# ASIC_3.net
KiCad netlist of a schematic drawn in Altium Designer
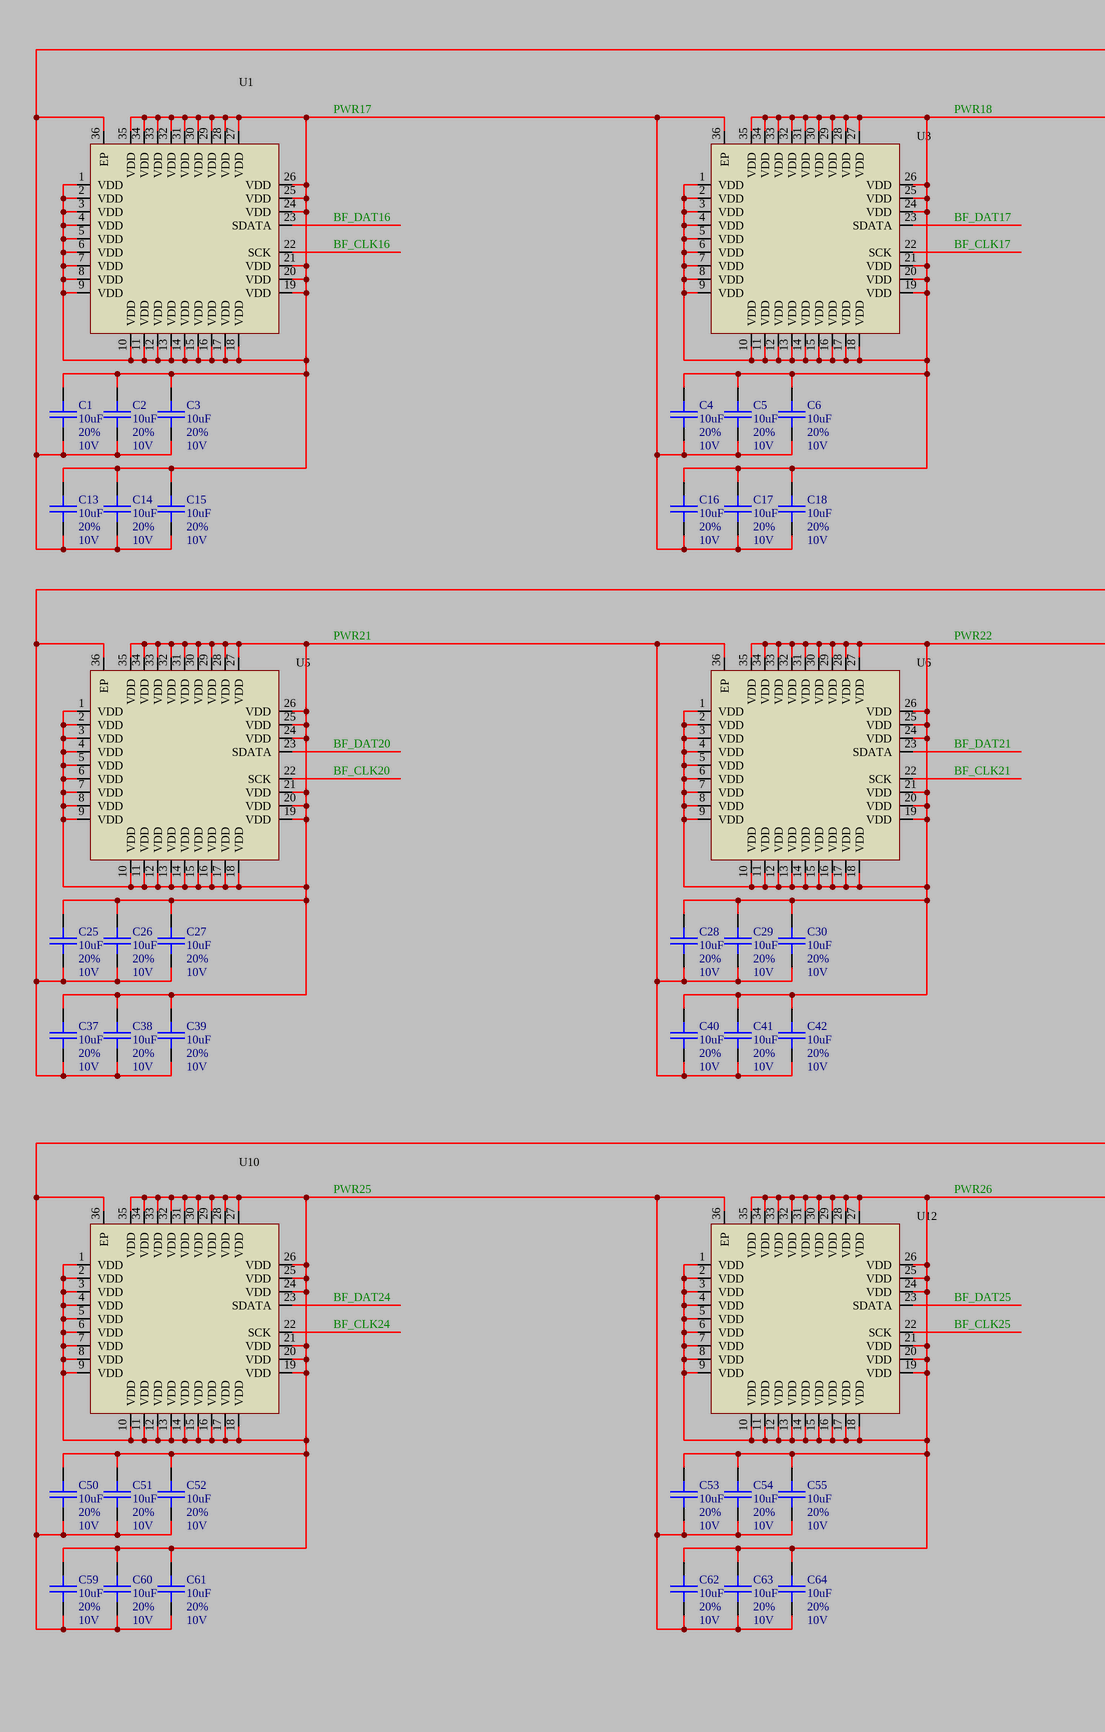
[diagram p0: ASIC_3.SchDoc, left]
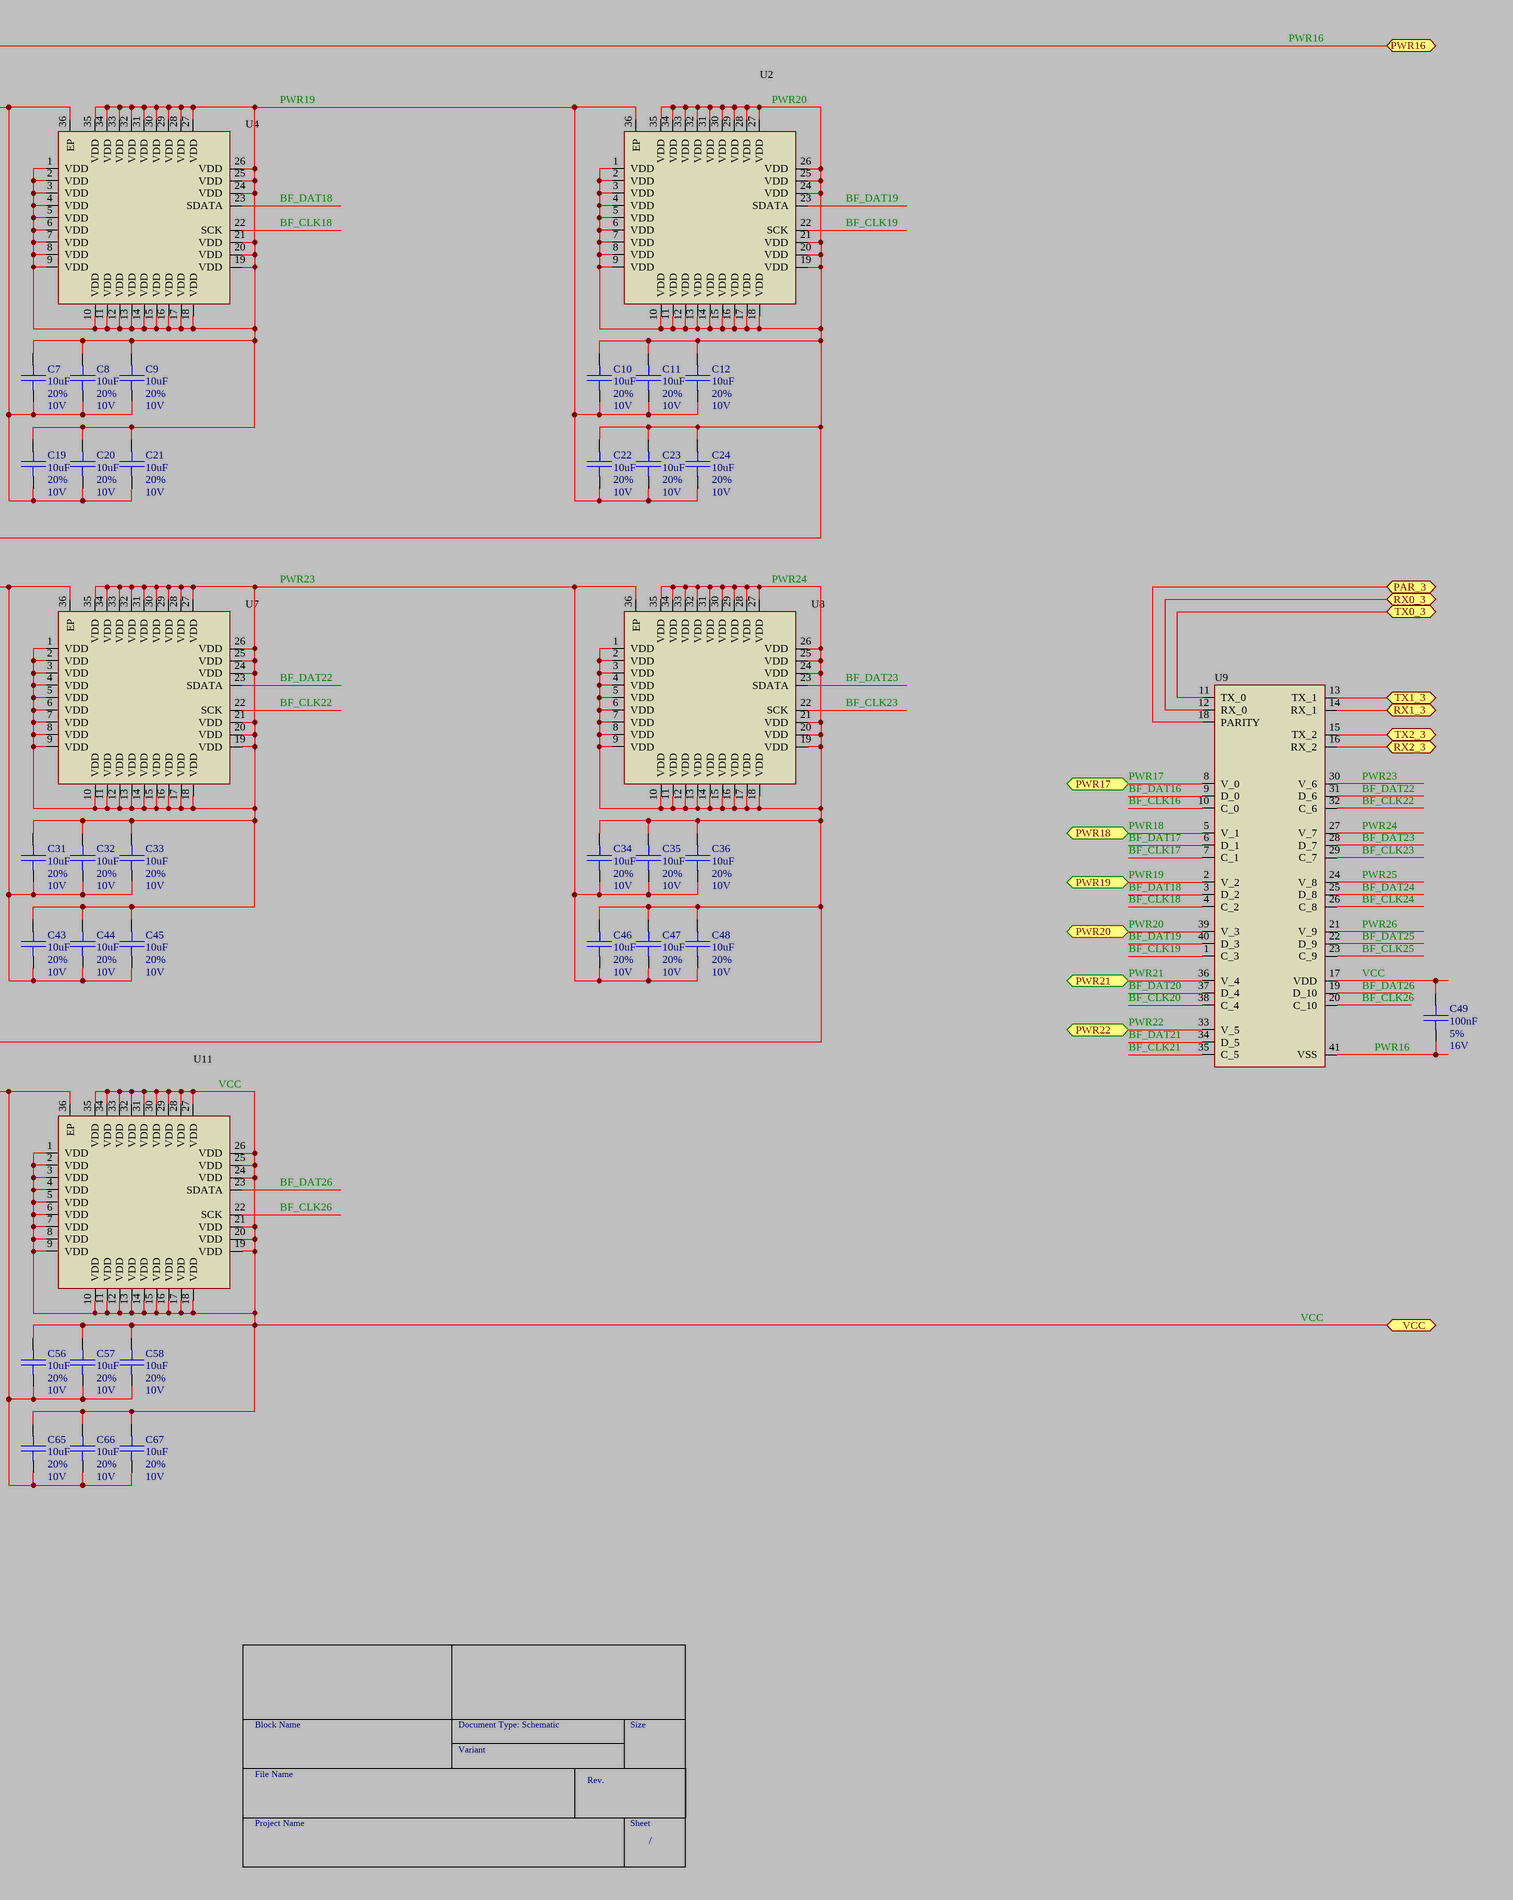
[diagram p1: ASIC_3.SchDoc, right]

(export (version "E")
  (design (tool "Eeschema 10.0.6"))
  (components
    (comp (ref "C1")
      (value "C")
      (footprint "SMD_0402_CAPC1005X70N")
      (fields
        (field (name "DB_PART_NUMBER") "CAP000047481")
        (field (name "DB_VALUE") "10uF")
        (field (name "DB_TOLERANCE") "20%")
        (field (name "DB_VOLTAGE") "10V")
        (field (name "DB_MANUFACTURER_PART") "SAMSUNG    CL05A106MP5NUNC")
        (field (name "DB_APPROVED_BY") "VSN")
      )
      (libsource (lib "Database_Libs1") (part "C"))
    )
    (comp (ref "C2")
      (value "C")
      (footprint "SMD_0402_CAPC1005X70N")
      (fields
        (field (name "DB_PART_NUMBER") "CAP000047481")
        (field (name "DB_VALUE") "10uF")
        (field (name "DB_TOLERANCE") "20%")
        (field (name "DB_VOLTAGE") "10V")
        (field (name "DB_MANUFACTURER_PART") "SAMSUNG    CL05A106MP5NUNC")
        (field (name "DB_APPROVED_BY") "VSN")
      )
      (libsource (lib "Database_Libs1") (part "C"))
    )
    (comp (ref "C3")
      (value "C")
      (footprint "SMD_0402_CAPC1005X70N")
      (fields
        (field (name "DB_PART_NUMBER") "CAP000047481")
        (field (name "DB_VALUE") "10uF")
        (field (name "DB_TOLERANCE") "20%")
        (field (name "DB_VOLTAGE") "10V")
        (field (name "DB_MANUFACTURER_PART") "SAMSUNG    CL05A106MP5NUNC")
        (field (name "DB_APPROVED_BY") "VSN")
      )
      (libsource (lib "Database_Libs1") (part "C"))
    )
    (comp (ref "C4")
      (value "C")
      (footprint "SMD_0402_CAPC1005X70N")
      (fields
        (field (name "DB_PART_NUMBER") "CAP000047481")
        (field (name "DB_VALUE") "10uF")
        (field (name "DB_TOLERANCE") "20%")
        (field (name "DB_VOLTAGE") "10V")
        (field (name "DB_MANUFACTURER_PART") "SAMSUNG    CL05A106MP5NUNC")
        (field (name "DB_APPROVED_BY") "VSN")
      )
      (libsource (lib "Database_Libs1") (part "C"))
    )
    (comp (ref "C5")
      (value "C")
      (footprint "SMD_0402_CAPC1005X70N")
      (fields
        (field (name "DB_PART_NUMBER") "CAP000047481")
        (field (name "DB_VALUE") "10uF")
        (field (name "DB_TOLERANCE") "20%")
        (field (name "DB_VOLTAGE") "10V")
        (field (name "DB_MANUFACTURER_PART") "SAMSUNG    CL05A106MP5NUNC")
        (field (name "DB_APPROVED_BY") "VSN")
      )
      (libsource (lib "Database_Libs1") (part "C"))
    )
    (comp (ref "C6")
      (value "C")
      (footprint "SMD_0402_CAPC1005X70N")
      (fields
        (field (name "DB_PART_NUMBER") "CAP000047481")
        (field (name "DB_VALUE") "10uF")
        (field (name "DB_TOLERANCE") "20%")
        (field (name "DB_VOLTAGE") "10V")
        (field (name "DB_MANUFACTURER_PART") "SAMSUNG    CL05A106MP5NUNC")
        (field (name "DB_APPROVED_BY") "VSN")
      )
      (libsource (lib "Database_Libs1") (part "C"))
    )
    (comp (ref "C7")
      (value "C")
      (footprint "SMD_0402_CAPC1005X70N")
      (fields
        (field (name "DB_PART_NUMBER") "CAP000047481")
        (field (name "DB_VALUE") "10uF")
        (field (name "DB_TOLERANCE") "20%")
        (field (name "DB_VOLTAGE") "10V")
        (field (name "DB_MANUFACTURER_PART") "SAMSUNG    CL05A106MP5NUNC")
        (field (name "DB_APPROVED_BY") "VSN")
      )
      (libsource (lib "Database_Libs1") (part "C"))
    )
    (comp (ref "C8")
      (value "C")
      (footprint "SMD_0402_CAPC1005X70N")
      (fields
        (field (name "DB_PART_NUMBER") "CAP000047481")
        (field (name "DB_VALUE") "10uF")
        (field (name "DB_TOLERANCE") "20%")
        (field (name "DB_VOLTAGE") "10V")
        (field (name "DB_MANUFACTURER_PART") "SAMSUNG    CL05A106MP5NUNC")
        (field (name "DB_APPROVED_BY") "VSN")
      )
      (libsource (lib "Database_Libs1") (part "C"))
    )
    (comp (ref "C9")
      (value "C")
      (footprint "SMD_0402_CAPC1005X70N")
      (fields
        (field (name "DB_PART_NUMBER") "CAP000047481")
        (field (name "DB_VALUE") "10uF")
        (field (name "DB_TOLERANCE") "20%")
        (field (name "DB_VOLTAGE") "10V")
        (field (name "DB_MANUFACTURER_PART") "SAMSUNG    CL05A106MP5NUNC")
        (field (name "DB_APPROVED_BY") "VSN")
      )
      (libsource (lib "Database_Libs1") (part "C"))
    )
    (comp (ref "C10")
      (value "C")
      (footprint "SMD_0402_CAPC1005X70N")
      (fields
        (field (name "DB_PART_NUMBER") "CAP000047481")
        (field (name "DB_VALUE") "10uF")
        (field (name "DB_TOLERANCE") "20%")
        (field (name "DB_VOLTAGE") "10V")
        (field (name "DB_MANUFACTURER_PART") "SAMSUNG    CL05A106MP5NUNC")
        (field (name "DB_APPROVED_BY") "VSN")
      )
      (libsource (lib "Database_Libs1") (part "C"))
    )
    (comp (ref "C11")
      (value "C")
      (footprint "SMD_0402_CAPC1005X70N")
      (fields
        (field (name "DB_PART_NUMBER") "CAP000047481")
        (field (name "DB_VALUE") "10uF")
        (field (name "DB_TOLERANCE") "20%")
        (field (name "DB_VOLTAGE") "10V")
        (field (name "DB_MANUFACTURER_PART") "SAMSUNG    CL05A106MP5NUNC")
        (field (name "DB_APPROVED_BY") "VSN")
      )
      (libsource (lib "Database_Libs1") (part "C"))
    )
    (comp (ref "C12")
      (value "C")
      (footprint "SMD_0402_CAPC1005X70N")
      (fields
        (field (name "DB_PART_NUMBER") "CAP000047481")
        (field (name "DB_VALUE") "10uF")
        (field (name "DB_TOLERANCE") "20%")
        (field (name "DB_VOLTAGE") "10V")
        (field (name "DB_MANUFACTURER_PART") "SAMSUNG    CL05A106MP5NUNC")
        (field (name "DB_APPROVED_BY") "VSN")
      )
      (libsource (lib "Database_Libs1") (part "C"))
    )
    (comp (ref "C13")
      (value "C")
      (footprint "SMD_0402_CAPC1005X70N")
      (fields
        (field (name "DB_PART_NUMBER") "CAP000047481")
        (field (name "DB_VALUE") "10uF")
        (field (name "DB_TOLERANCE") "20%")
        (field (name "DB_VOLTAGE") "10V")
        (field (name "DB_MANUFACTURER_PART") "SAMSUNG    CL05A106MP5NUNC")
        (field (name "DB_APPROVED_BY") "VSN")
      )
      (libsource (lib "Database_Libs1") (part "C"))
    )
    (comp (ref "C14")
      (value "C")
      (footprint "SMD_0402_CAPC1005X70N")
      (fields
        (field (name "DB_PART_NUMBER") "CAP000047481")
        (field (name "DB_VALUE") "10uF")
        (field (name "DB_TOLERANCE") "20%")
        (field (name "DB_VOLTAGE") "10V")
        (field (name "DB_MANUFACTURER_PART") "SAMSUNG    CL05A106MP5NUNC")
        (field (name "DB_APPROVED_BY") "VSN")
      )
      (libsource (lib "Database_Libs1") (part "C"))
    )
    (comp (ref "C15")
      (value "C")
      (footprint "SMD_0402_CAPC1005X70N")
      (fields
        (field (name "DB_PART_NUMBER") "CAP000047481")
        (field (name "DB_VALUE") "10uF")
        (field (name "DB_TOLERANCE") "20%")
        (field (name "DB_VOLTAGE") "10V")
        (field (name "DB_MANUFACTURER_PART") "SAMSUNG    CL05A106MP5NUNC")
        (field (name "DB_APPROVED_BY") "VSN")
      )
      (libsource (lib "Database_Libs1") (part "C"))
    )
    (comp (ref "C16")
      (value "C")
      (footprint "SMD_0402_CAPC1005X70N")
      (fields
        (field (name "DB_PART_NUMBER") "CAP000047481")
        (field (name "DB_VALUE") "10uF")
        (field (name "DB_TOLERANCE") "20%")
        (field (name "DB_VOLTAGE") "10V")
        (field (name "DB_MANUFACTURER_PART") "SAMSUNG    CL05A106MP5NUNC")
        (field (name "DB_APPROVED_BY") "VSN")
      )
      (libsource (lib "Database_Libs1") (part "C"))
    )
    (comp (ref "C17")
      (value "C")
      (footprint "SMD_0402_CAPC1005X70N")
      (fields
        (field (name "DB_PART_NUMBER") "CAP000047481")
        (field (name "DB_VALUE") "10uF")
        (field (name "DB_TOLERANCE") "20%")
        (field (name "DB_VOLTAGE") "10V")
        (field (name "DB_MANUFACTURER_PART") "SAMSUNG    CL05A106MP5NUNC")
        (field (name "DB_APPROVED_BY") "VSN")
      )
      (libsource (lib "Database_Libs1") (part "C"))
    )
    (comp (ref "C18")
      (value "C")
      (footprint "SMD_0402_CAPC1005X70N")
      (fields
        (field (name "DB_PART_NUMBER") "CAP000047481")
        (field (name "DB_VALUE") "10uF")
        (field (name "DB_TOLERANCE") "20%")
        (field (name "DB_VOLTAGE") "10V")
        (field (name "DB_MANUFACTURER_PART") "SAMSUNG    CL05A106MP5NUNC")
        (field (name "DB_APPROVED_BY") "VSN")
      )
      (libsource (lib "Database_Libs1") (part "C"))
    )
    (comp (ref "C19")
      (value "C")
      (footprint "SMD_0402_CAPC1005X70N")
      (fields
        (field (name "DB_PART_NUMBER") "CAP000047481")
        (field (name "DB_VALUE") "10uF")
        (field (name "DB_TOLERANCE") "20%")
        (field (name "DB_VOLTAGE") "10V")
        (field (name "DB_MANUFACTURER_PART") "SAMSUNG    CL05A106MP5NUNC")
        (field (name "DB_APPROVED_BY") "VSN")
      )
      (libsource (lib "Database_Libs1") (part "C"))
    )
    (comp (ref "C20")
      (value "C")
      (footprint "SMD_0402_CAPC1005X70N")
      (fields
        (field (name "DB_PART_NUMBER") "CAP000047481")
        (field (name "DB_VALUE") "10uF")
        (field (name "DB_TOLERANCE") "20%")
        (field (name "DB_VOLTAGE") "10V")
        (field (name "DB_MANUFACTURER_PART") "SAMSUNG    CL05A106MP5NUNC")
        (field (name "DB_APPROVED_BY") "VSN")
      )
      (libsource (lib "Database_Libs1") (part "C"))
    )
    (comp (ref "C21")
      (value "C")
      (footprint "SMD_0402_CAPC1005X70N")
      (fields
        (field (name "DB_PART_NUMBER") "CAP000047481")
        (field (name "DB_VALUE") "10uF")
        (field (name "DB_TOLERANCE") "20%")
        (field (name "DB_VOLTAGE") "10V")
        (field (name "DB_MANUFACTURER_PART") "SAMSUNG    CL05A106MP5NUNC")
        (field (name "DB_APPROVED_BY") "VSN")
      )
      (libsource (lib "Database_Libs1") (part "C"))
    )
    (comp (ref "C22")
      (value "C")
      (footprint "SMD_0402_CAPC1005X70N")
      (fields
        (field (name "DB_PART_NUMBER") "CAP000047481")
        (field (name "DB_VALUE") "10uF")
        (field (name "DB_TOLERANCE") "20%")
        (field (name "DB_VOLTAGE") "10V")
        (field (name "DB_MANUFACTURER_PART") "SAMSUNG    CL05A106MP5NUNC")
        (field (name "DB_APPROVED_BY") "VSN")
      )
      (libsource (lib "Database_Libs1") (part "C"))
    )
    (comp (ref "C23")
      (value "C")
      (footprint "SMD_0402_CAPC1005X70N")
      (fields
        (field (name "DB_PART_NUMBER") "CAP000047481")
        (field (name "DB_VALUE") "10uF")
        (field (name "DB_TOLERANCE") "20%")
        (field (name "DB_VOLTAGE") "10V")
        (field (name "DB_MANUFACTURER_PART") "SAMSUNG    CL05A106MP5NUNC")
        (field (name "DB_APPROVED_BY") "VSN")
      )
      (libsource (lib "Database_Libs1") (part "C"))
    )
    (comp (ref "C24")
      (value "C")
      (footprint "SMD_0402_CAPC1005X70N")
      (fields
        (field (name "DB_PART_NUMBER") "CAP000047481")
        (field (name "DB_VALUE") "10uF")
        (field (name "DB_TOLERANCE") "20%")
        (field (name "DB_VOLTAGE") "10V")
        (field (name "DB_MANUFACTURER_PART") "SAMSUNG    CL05A106MP5NUNC")
        (field (name "DB_APPROVED_BY") "VSN")
      )
      (libsource (lib "Database_Libs1") (part "C"))
    )
    (comp (ref "C25")
      (value "C")
      (footprint "SMD_0402_CAPC1005X70N")
      (fields
        (field (name "DB_PART_NUMBER") "CAP000047481")
        (field (name "DB_VALUE") "10uF")
        (field (name "DB_TOLERANCE") "20%")
        (field (name "DB_VOLTAGE") "10V")
        (field (name "DB_MANUFACTURER_PART") "SAMSUNG    CL05A106MP5NUNC")
        (field (name "DB_APPROVED_BY") "VSN")
      )
      (libsource (lib "Database_Libs1") (part "C"))
    )
    (comp (ref "C26")
      (value "C")
      (footprint "SMD_0402_CAPC1005X70N")
      (fields
        (field (name "DB_PART_NUMBER") "CAP000047481")
        (field (name "DB_VALUE") "10uF")
        (field (name "DB_TOLERANCE") "20%")
        (field (name "DB_VOLTAGE") "10V")
        (field (name "DB_MANUFACTURER_PART") "SAMSUNG    CL05A106MP5NUNC")
        (field (name "DB_APPROVED_BY") "VSN")
      )
      (libsource (lib "Database_Libs1") (part "C"))
    )
    (comp (ref "C27")
      (value "C")
      (footprint "SMD_0402_CAPC1005X70N")
      (fields
        (field (name "DB_PART_NUMBER") "CAP000047481")
        (field (name "DB_VALUE") "10uF")
        (field (name "DB_TOLERANCE") "20%")
        (field (name "DB_VOLTAGE") "10V")
        (field (name "DB_MANUFACTURER_PART") "SAMSUNG    CL05A106MP5NUNC")
        (field (name "DB_APPROVED_BY") "VSN")
      )
      (libsource (lib "Database_Libs1") (part "C"))
    )
    (comp (ref "C28")
      (value "C")
      (footprint "SMD_0402_CAPC1005X70N")
      (fields
        (field (name "DB_PART_NUMBER") "CAP000047481")
        (field (name "DB_VALUE") "10uF")
        (field (name "DB_TOLERANCE") "20%")
        (field (name "DB_VOLTAGE") "10V")
        (field (name "DB_MANUFACTURER_PART") "SAMSUNG    CL05A106MP5NUNC")
        (field (name "DB_APPROVED_BY") "VSN")
      )
      (libsource (lib "Database_Libs1") (part "C"))
    )
    (comp (ref "C29")
      (value "C")
      (footprint "SMD_0402_CAPC1005X70N")
      (fields
        (field (name "DB_PART_NUMBER") "CAP000047481")
        (field (name "DB_VALUE") "10uF")
        (field (name "DB_TOLERANCE") "20%")
        (field (name "DB_VOLTAGE") "10V")
        (field (name "DB_MANUFACTURER_PART") "SAMSUNG    CL05A106MP5NUNC")
        (field (name "DB_APPROVED_BY") "VSN")
      )
      (libsource (lib "Database_Libs1") (part "C"))
    )
    (comp (ref "C30")
      (value "C")
      (footprint "SMD_0402_CAPC1005X70N")
      (fields
        (field (name "DB_PART_NUMBER") "CAP000047481")
        (field (name "DB_VALUE") "10uF")
        (field (name "DB_TOLERANCE") "20%")
        (field (name "DB_VOLTAGE") "10V")
        (field (name "DB_MANUFACTURER_PART") "SAMSUNG    CL05A106MP5NUNC")
        (field (name "DB_APPROVED_BY") "VSN")
      )
      (libsource (lib "Database_Libs1") (part "C"))
    )
    (comp (ref "C31")
      (value "C")
      (footprint "SMD_0402_CAPC1005X70N")
      (fields
        (field (name "DB_PART_NUMBER") "CAP000047481")
        (field (name "DB_VALUE") "10uF")
        (field (name "DB_TOLERANCE") "20%")
        (field (name "DB_VOLTAGE") "10V")
        (field (name "DB_MANUFACTURER_PART") "SAMSUNG    CL05A106MP5NUNC")
        (field (name "DB_APPROVED_BY") "VSN")
      )
      (libsource (lib "Database_Libs1") (part "C"))
    )
    (comp (ref "C32")
      (value "C")
      (footprint "SMD_0402_CAPC1005X70N")
      (fields
        (field (name "DB_PART_NUMBER") "CAP000047481")
        (field (name "DB_VALUE") "10uF")
        (field (name "DB_TOLERANCE") "20%")
        (field (name "DB_VOLTAGE") "10V")
        (field (name "DB_MANUFACTURER_PART") "SAMSUNG    CL05A106MP5NUNC")
        (field (name "DB_APPROVED_BY") "VSN")
      )
      (libsource (lib "Database_Libs1") (part "C"))
    )
    (comp (ref "C33")
      (value "C")
      (footprint "SMD_0402_CAPC1005X70N")
      (fields
        (field (name "DB_PART_NUMBER") "CAP000047481")
        (field (name "DB_VALUE") "10uF")
        (field (name "DB_TOLERANCE") "20%")
        (field (name "DB_VOLTAGE") "10V")
        (field (name "DB_MANUFACTURER_PART") "SAMSUNG    CL05A106MP5NUNC")
        (field (name "DB_APPROVED_BY") "VSN")
      )
      (libsource (lib "Database_Libs1") (part "C"))
    )
    (comp (ref "C34")
      (value "C")
      (footprint "SMD_0402_CAPC1005X70N")
      (fields
        (field (name "DB_PART_NUMBER") "CAP000047481")
        (field (name "DB_VALUE") "10uF")
        (field (name "DB_TOLERANCE") "20%")
        (field (name "DB_VOLTAGE") "10V")
        (field (name "DB_MANUFACTURER_PART") "SAMSUNG    CL05A106MP5NUNC")
        (field (name "DB_APPROVED_BY") "VSN")
      )
      (libsource (lib "Database_Libs1") (part "C"))
    )
    (comp (ref "C35")
      (value "C")
      (footprint "SMD_0402_CAPC1005X70N")
      (fields
        (field (name "DB_PART_NUMBER") "CAP000047481")
        (field (name "DB_VALUE") "10uF")
        (field (name "DB_TOLERANCE") "20%")
        (field (name "DB_VOLTAGE") "10V")
        (field (name "DB_MANUFACTURER_PART") "SAMSUNG    CL05A106MP5NUNC")
        (field (name "DB_APPROVED_BY") "VSN")
      )
      (libsource (lib "Database_Libs1") (part "C"))
    )
    (comp (ref "C36")
      (value "C")
      (footprint "SMD_0402_CAPC1005X70N")
      (fields
        (field (name "DB_PART_NUMBER") "CAP000047481")
        (field (name "DB_VALUE") "10uF")
        (field (name "DB_TOLERANCE") "20%")
        (field (name "DB_VOLTAGE") "10V")
        (field (name "DB_MANUFACTURER_PART") "SAMSUNG    CL05A106MP5NUNC")
        (field (name "DB_APPROVED_BY") "VSN")
      )
      (libsource (lib "Database_Libs1") (part "C"))
    )
    (comp (ref "C37")
      (value "C")
      (footprint "SMD_0402_CAPC1005X70N")
      (fields
        (field (name "DB_PART_NUMBER") "CAP000047481")
        (field (name "DB_VALUE") "10uF")
        (field (name "DB_TOLERANCE") "20%")
        (field (name "DB_VOLTAGE") "10V")
        (field (name "DB_MANUFACTURER_PART") "SAMSUNG    CL05A106MP5NUNC")
        (field (name "DB_APPROVED_BY") "VSN")
      )
      (libsource (lib "Database_Libs1") (part "C"))
    )
    (comp (ref "C38")
      (value "C")
      (footprint "SMD_0402_CAPC1005X70N")
      (fields
        (field (name "DB_PART_NUMBER") "CAP000047481")
        (field (name "DB_VALUE") "10uF")
        (field (name "DB_TOLERANCE") "20%")
        (field (name "DB_VOLTAGE") "10V")
        (field (name "DB_MANUFACTURER_PART") "SAMSUNG    CL05A106MP5NUNC")
        (field (name "DB_APPROVED_BY") "VSN")
      )
      (libsource (lib "Database_Libs1") (part "C"))
    )
    (comp (ref "C39")
      (value "C")
      (footprint "SMD_0402_CAPC1005X70N")
      (fields
        (field (name "DB_PART_NUMBER") "CAP000047481")
        (field (name "DB_VALUE") "10uF")
        (field (name "DB_TOLERANCE") "20%")
        (field (name "DB_VOLTAGE") "10V")
        (field (name "DB_MANUFACTURER_PART") "SAMSUNG    CL05A106MP5NUNC")
        (field (name "DB_APPROVED_BY") "VSN")
      )
      (libsource (lib "Database_Libs1") (part "C"))
    )
    (comp (ref "C40")
      (value "C")
      (footprint "SMD_0402_CAPC1005X70N")
      (fields
        (field (name "DB_PART_NUMBER") "CAP000047481")
        (field (name "DB_VALUE") "10uF")
        (field (name "DB_TOLERANCE") "20%")
        (field (name "DB_VOLTAGE") "10V")
        (field (name "DB_MANUFACTURER_PART") "SAMSUNG    CL05A106MP5NUNC")
        (field (name "DB_APPROVED_BY") "VSN")
      )
      (libsource (lib "Database_Libs1") (part "C"))
    )
    (comp (ref "C41")
      (value "C")
      (footprint "SMD_0402_CAPC1005X70N")
      (fields
        (field (name "DB_PART_NUMBER") "CAP000047481")
        (field (name "DB_VALUE") "10uF")
        (field (name "DB_TOLERANCE") "20%")
        (field (name "DB_VOLTAGE") "10V")
        (field (name "DB_MANUFACTURER_PART") "SAMSUNG    CL05A106MP5NUNC")
        (field (name "DB_APPROVED_BY") "VSN")
      )
      (libsource (lib "Database_Libs1") (part "C"))
    )
    (comp (ref "C42")
      (value "C")
      (footprint "SMD_0402_CAPC1005X70N")
      (fields
        (field (name "DB_PART_NUMBER") "CAP000047481")
        (field (name "DB_VALUE") "10uF")
        (field (name "DB_TOLERANCE") "20%")
        (field (name "DB_VOLTAGE") "10V")
        (field (name "DB_MANUFACTURER_PART") "SAMSUNG    CL05A106MP5NUNC")
        (field (name "DB_APPROVED_BY") "VSN")
      )
      (libsource (lib "Database_Libs1") (part "C"))
    )
    (comp (ref "C43")
      (value "C")
      (footprint "SMD_0402_CAPC1005X70N")
      (fields
        (field (name "DB_PART_NUMBER") "CAP000047481")
        (field (name "DB_VALUE") "10uF")
        (field (name "DB_TOLERANCE") "20%")
        (field (name "DB_VOLTAGE") "10V")
        (field (name "DB_MANUFACTURER_PART") "SAMSUNG    CL05A106MP5NUNC")
        (field (name "DB_APPROVED_BY") "VSN")
      )
      (libsource (lib "Database_Libs1") (part "C"))
    )
    (comp (ref "C44")
      (value "C")
      (footprint "SMD_0402_CAPC1005X70N")
      (fields
        (field (name "DB_PART_NUMBER") "CAP000047481")
        (field (name "DB_VALUE") "10uF")
        (field (name "DB_TOLERANCE") "20%")
        (field (name "DB_VOLTAGE") "10V")
        (field (name "DB_MANUFACTURER_PART") "SAMSUNG    CL05A106MP5NUNC")
        (field (name "DB_APPROVED_BY") "VSN")
      )
      (libsource (lib "Database_Libs1") (part "C"))
    )
    (comp (ref "C45")
      (value "C")
      (footprint "SMD_0402_CAPC1005X70N")
      (fields
        (field (name "DB_PART_NUMBER") "CAP000047481")
        (field (name "DB_VALUE") "10uF")
        (field (name "DB_TOLERANCE") "20%")
        (field (name "DB_VOLTAGE") "10V")
        (field (name "DB_MANUFACTURER_PART") "SAMSUNG    CL05A106MP5NUNC")
        (field (name "DB_APPROVED_BY") "VSN")
      )
      (libsource (lib "Database_Libs1") (part "C"))
    )
    (comp (ref "C46")
      (value "C")
      (footprint "SMD_0402_CAPC1005X70N")
      (fields
        (field (name "DB_PART_NUMBER") "CAP000047481")
        (field (name "DB_VALUE") "10uF")
        (field (name "DB_TOLERANCE") "20%")
        (field (name "DB_VOLTAGE") "10V")
        (field (name "DB_MANUFACTURER_PART") "SAMSUNG    CL05A106MP5NUNC")
        (field (name "DB_APPROVED_BY") "VSN")
      )
      (libsource (lib "Database_Libs1") (part "C"))
    )
    (comp (ref "C47")
      (value "C")
      (footprint "SMD_0402_CAPC1005X70N")
      (fields
        (field (name "DB_PART_NUMBER") "CAP000047481")
        (field (name "DB_VALUE") "10uF")
        (field (name "DB_TOLERANCE") "20%")
        (field (name "DB_VOLTAGE") "10V")
        (field (name "DB_MANUFACTURER_PART") "SAMSUNG    CL05A106MP5NUNC")
        (field (name "DB_APPROVED_BY") "VSN")
      )
      (libsource (lib "Database_Libs1") (part "C"))
    )
    (comp (ref "C48")
      (value "C")
      (footprint "SMD_0402_CAPC1005X70N")
      (fields
        (field (name "DB_PART_NUMBER") "CAP000047481")
        (field (name "DB_VALUE") "10uF")
        (field (name "DB_TOLERANCE") "20%")
        (field (name "DB_VOLTAGE") "10V")
        (field (name "DB_MANUFACTURER_PART") "SAMSUNG    CL05A106MP5NUNC")
        (field (name "DB_APPROVED_BY") "VSN")
      )
      (libsource (lib "Database_Libs1") (part "C"))
    )
    (comp (ref "C49")
      (value "C")
      (footprint "SMD_0603_CAPC1608X95N")
      (fields
        (field (name "DB_PART_NUMBER") "CAP000027134")
        (field (name "DB_VALUE") "100nF")
        (field (name "DB_TOLERANCE") "5%")
        (field (name "DB_VOLTAGE") "16V")
        (field (name "DB_MANUFACTURER_PART") "KEMET    C0603C104J4RAC")
      )
      (libsource (lib "Database_Libs1") (part "C"))
    )
    (comp (ref "C50")
      (value "C")
      (footprint "SMD_0402_CAPC1005X70N")
      (fields
        (field (name "DB_PART_NUMBER") "CAP000047481")
        (field (name "DB_VALUE") "10uF")
        (field (name "DB_TOLERANCE") "20%")
        (field (name "DB_VOLTAGE") "10V")
        (field (name "DB_MANUFACTURER_PART") "SAMSUNG    CL05A106MP5NUNC")
        (field (name "DB_APPROVED_BY") "VSN")
      )
      (libsource (lib "Database_Libs1") (part "C"))
    )
    (comp (ref "C51")
      (value "C")
      (footprint "SMD_0402_CAPC1005X70N")
      (fields
        (field (name "DB_PART_NUMBER") "CAP000047481")
        (field (name "DB_VALUE") "10uF")
        (field (name "DB_TOLERANCE") "20%")
        (field (name "DB_VOLTAGE") "10V")
        (field (name "DB_MANUFACTURER_PART") "SAMSUNG    CL05A106MP5NUNC")
        (field (name "DB_APPROVED_BY") "VSN")
      )
      (libsource (lib "Database_Libs1") (part "C"))
    )
    (comp (ref "C52")
      (value "C")
      (footprint "SMD_0402_CAPC1005X70N")
      (fields
        (field (name "DB_PART_NUMBER") "CAP000047481")
        (field (name "DB_VALUE") "10uF")
        (field (name "DB_TOLERANCE") "20%")
        (field (name "DB_VOLTAGE") "10V")
        (field (name "DB_MANUFACTURER_PART") "SAMSUNG    CL05A106MP5NUNC")
        (field (name "DB_APPROVED_BY") "VSN")
      )
      (libsource (lib "Database_Libs1") (part "C"))
    )
    (comp (ref "C53")
      (value "C")
      (footprint "SMD_0402_CAPC1005X70N")
      (fields
        (field (name "DB_PART_NUMBER") "CAP000047481")
        (field (name "DB_VALUE") "10uF")
        (field (name "DB_TOLERANCE") "20%")
        (field (name "DB_VOLTAGE") "10V")
        (field (name "DB_MANUFACTURER_PART") "SAMSUNG    CL05A106MP5NUNC")
        (field (name "DB_APPROVED_BY") "VSN")
      )
      (libsource (lib "Database_Libs1") (part "C"))
    )
    (comp (ref "C54")
      (value "C")
      (footprint "SMD_0402_CAPC1005X70N")
      (fields
        (field (name "DB_PART_NUMBER") "CAP000047481")
        (field (name "DB_VALUE") "10uF")
        (field (name "DB_TOLERANCE") "20%")
        (field (name "DB_VOLTAGE") "10V")
        (field (name "DB_MANUFACTURER_PART") "SAMSUNG    CL05A106MP5NUNC")
        (field (name "DB_APPROVED_BY") "VSN")
      )
      (libsource (lib "Database_Libs1") (part "C"))
    )
    (comp (ref "C55")
      (value "C")
      (footprint "SMD_0402_CAPC1005X70N")
      (fields
        (field (name "DB_PART_NUMBER") "CAP000047481")
        (field (name "DB_VALUE") "10uF")
        (field (name "DB_TOLERANCE") "20%")
        (field (name "DB_VOLTAGE") "10V")
        (field (name "DB_MANUFACTURER_PART") "SAMSUNG    CL05A106MP5NUNC")
        (field (name "DB_APPROVED_BY") "VSN")
      )
      (libsource (lib "Database_Libs1") (part "C"))
    )
    (comp (ref "C56")
      (value "C")
      (footprint "SMD_0402_CAPC1005X70N")
      (fields
        (field (name "DB_PART_NUMBER") "CAP000047481")
        (field (name "DB_VALUE") "10uF")
        (field (name "DB_TOLERANCE") "20%")
        (field (name "DB_VOLTAGE") "10V")
        (field (name "DB_MANUFACTURER_PART") "SAMSUNG    CL05A106MP5NUNC")
        (field (name "DB_APPROVED_BY") "VSN")
      )
      (libsource (lib "Database_Libs1") (part "C"))
    )
    (comp (ref "C57")
      (value "C")
      (footprint "SMD_0402_CAPC1005X70N")
      (fields
        (field (name "DB_PART_NUMBER") "CAP000047481")
        (field (name "DB_VALUE") "10uF")
        (field (name "DB_TOLERANCE") "20%")
        (field (name "DB_VOLTAGE") "10V")
        (field (name "DB_MANUFACTURER_PART") "SAMSUNG    CL05A106MP5NUNC")
        (field (name "DB_APPROVED_BY") "VSN")
      )
      (libsource (lib "Database_Libs1") (part "C"))
    )
    (comp (ref "C58")
      (value "C")
      (footprint "SMD_0402_CAPC1005X70N")
      (fields
        (field (name "DB_PART_NUMBER") "CAP000047481")
        (field (name "DB_VALUE") "10uF")
        (field (name "DB_TOLERANCE") "20%")
        (field (name "DB_VOLTAGE") "10V")
        (field (name "DB_MANUFACTURER_PART") "SAMSUNG    CL05A106MP5NUNC")
        (field (name "DB_APPROVED_BY") "VSN")
      )
      (libsource (lib "Database_Libs1") (part "C"))
    )
    (comp (ref "C59")
      (value "C")
      (footprint "SMD_0402_CAPC1005X70N")
      (fields
        (field (name "DB_PART_NUMBER") "CAP000047481")
        (field (name "DB_VALUE") "10uF")
        (field (name "DB_TOLERANCE") "20%")
        (field (name "DB_VOLTAGE") "10V")
        (field (name "DB_MANUFACTURER_PART") "SAMSUNG    CL05A106MP5NUNC")
        (field (name "DB_APPROVED_BY") "VSN")
      )
      (libsource (lib "Database_Libs1") (part "C"))
    )
    (comp (ref "C60")
      (value "C")
      (footprint "SMD_0402_CAPC1005X70N")
      (fields
        (field (name "DB_PART_NUMBER") "CAP000047481")
        (field (name "DB_VALUE") "10uF")
        (field (name "DB_TOLERANCE") "20%")
        (field (name "DB_VOLTAGE") "10V")
        (field (name "DB_MANUFACTURER_PART") "SAMSUNG    CL05A106MP5NUNC")
        (field (name "DB_APPROVED_BY") "VSN")
      )
      (libsource (lib "Database_Libs1") (part "C"))
    )
    (comp (ref "C61")
      (value "C")
      (footprint "SMD_0402_CAPC1005X70N")
      (fields
        (field (name "DB_PART_NUMBER") "CAP000047481")
        (field (name "DB_VALUE") "10uF")
        (field (name "DB_TOLERANCE") "20%")
        (field (name "DB_VOLTAGE") "10V")
        (field (name "DB_MANUFACTURER_PART") "SAMSUNG    CL05A106MP5NUNC")
        (field (name "DB_APPROVED_BY") "VSN")
      )
      (libsource (lib "Database_Libs1") (part "C"))
    )
    (comp (ref "C62")
      (value "C")
      (footprint "SMD_0402_CAPC1005X70N")
      (fields
        (field (name "DB_PART_NUMBER") "CAP000047481")
        (field (name "DB_VALUE") "10uF")
        (field (name "DB_TOLERANCE") "20%")
        (field (name "DB_VOLTAGE") "10V")
        (field (name "DB_MANUFACTURER_PART") "SAMSUNG    CL05A106MP5NUNC")
        (field (name "DB_APPROVED_BY") "VSN")
      )
      (libsource (lib "Database_Libs1") (part "C"))
    )
    (comp (ref "C63")
      (value "C")
      (footprint "SMD_0402_CAPC1005X70N")
      (fields
        (field (name "DB_PART_NUMBER") "CAP000047481")
        (field (name "DB_VALUE") "10uF")
        (field (name "DB_TOLERANCE") "20%")
        (field (name "DB_VOLTAGE") "10V")
        (field (name "DB_MANUFACTURER_PART") "SAMSUNG    CL05A106MP5NUNC")
        (field (name "DB_APPROVED_BY") "VSN")
      )
      (libsource (lib "Database_Libs1") (part "C"))
    )
    (comp (ref "C64")
      (value "C")
      (footprint "SMD_0402_CAPC1005X70N")
      (fields
        (field (name "DB_PART_NUMBER") "CAP000047481")
        (field (name "DB_VALUE") "10uF")
        (field (name "DB_TOLERANCE") "20%")
        (field (name "DB_VOLTAGE") "10V")
        (field (name "DB_MANUFACTURER_PART") "SAMSUNG    CL05A106MP5NUNC")
        (field (name "DB_APPROVED_BY") "VSN")
      )
      (libsource (lib "Database_Libs1") (part "C"))
    )
    (comp (ref "C65")
      (value "C")
      (footprint "SMD_0402_CAPC1005X70N")
      (fields
        (field (name "DB_PART_NUMBER") "CAP000047481")
        (field (name "DB_VALUE") "10uF")
        (field (name "DB_TOLERANCE") "20%")
        (field (name "DB_VOLTAGE") "10V")
        (field (name "DB_MANUFACTURER_PART") "SAMSUNG    CL05A106MP5NUNC")
        (field (name "DB_APPROVED_BY") "VSN")
      )
      (libsource (lib "Database_Libs1") (part "C"))
    )
    (comp (ref "C66")
      (value "C")
      (footprint "SMD_0402_CAPC1005X70N")
      (fields
        (field (name "DB_PART_NUMBER") "CAP000047481")
        (field (name "DB_VALUE") "10uF")
        (field (name "DB_TOLERANCE") "20%")
        (field (name "DB_VOLTAGE") "10V")
        (field (name "DB_MANUFACTURER_PART") "SAMSUNG    CL05A106MP5NUNC")
        (field (name "DB_APPROVED_BY") "VSN")
      )
      (libsource (lib "Database_Libs1") (part "C"))
    )
    (comp (ref "C67")
      (value "C")
      (footprint "SMD_0402_CAPC1005X70N")
      (fields
        (field (name "DB_PART_NUMBER") "CAP000047481")
        (field (name "DB_VALUE") "10uF")
        (field (name "DB_TOLERANCE") "20%")
        (field (name "DB_VOLTAGE") "10V")
        (field (name "DB_MANUFACTURER_PART") "SAMSUNG    CL05A106MP5NUNC")
        (field (name "DB_APPROVED_BY") "VSN")
      )
      (libsource (lib "Database_Libs1") (part "C"))
    )
    (comp (ref "U1")
      (value "IC_BITFURY16")
      (footprint "SMD_QFN50P600X600X175-36AN")
      (description "BitFury 2016 16 nm")
      (libsource (lib "BitCoin") (part "IC_BITFURY16"))
    )
    (comp (ref "U2")
      (value "IC_BITFURY16")
      (footprint "SMD_QFN50P600X600X175-36AN")
      (description "BitFury 2016 16 nm")
      (libsource (lib "BitCoin") (part "IC_BITFURY16"))
    )
    (comp (ref "U3")
      (value "IC_BITFURY16")
      (footprint "SMD_QFN50P600X600X175-36AN")
      (description "BitFury 2016 16 nm")
      (libsource (lib "BitCoin") (part "IC_BITFURY16"))
    )
    (comp (ref "U4")
      (value "IC_BITFURY16")
      (footprint "SMD_QFN50P600X600X175-36AN")
      (description "BitFury 2016 16 nm")
      (libsource (lib "BitCoin") (part "IC_BITFURY16"))
    )
    (comp (ref "U5")
      (value "IC_BITFURY16")
      (footprint "SMD_QFN50P600X600X175-36AN")
      (description "BitFury 2016 16 nm")
      (libsource (lib "BitCoin") (part "IC_BITFURY16"))
    )
    (comp (ref "U6")
      (value "IC_BITFURY16")
      (footprint "SMD_QFN50P600X600X175-36AN")
      (description "BitFury 2016 16 nm")
      (libsource (lib "BitCoin") (part "IC_BITFURY16"))
    )
    (comp (ref "U7")
      (value "IC_BITFURY16")
      (footprint "SMD_QFN50P600X600X175-36AN")
      (description "BitFury 2016 16 nm")
      (libsource (lib "BitCoin") (part "IC_BITFURY16"))
    )
    (comp (ref "U8")
      (value "IC_BITFURY16")
      (footprint "SMD_QFN50P600X600X175-36AN")
      (description "BitFury 2016 16 nm")
      (libsource (lib "BitCoin") (part "IC_BITFURY16"))
    )
    (comp (ref "U9")
      (value "IC_BTC250")
      (footprint "SMD_QFN40P500X500X80-41N")
      (fields (field (name "DB_MANUFACTURER_PART") "BTC250 QFN40 EP"))
      (libsource (lib "BitCoin") (part "IC_BTC250"))
    )
    (comp (ref "U10")
      (value "IC_BITFURY16")
      (footprint "SMD_QFN50P600X600X175-36AN")
      (description "BitFury 2016 16 nm")
      (libsource (lib "BitCoin") (part "IC_BITFURY16"))
    )
    (comp (ref "U11")
      (value "IC_BITFURY16")
      (footprint "SMD_QFN50P600X600X175-36AN")
      (description "BitFury 2016 16 nm")
      (libsource (lib "BitCoin") (part "IC_BITFURY16"))
    )
    (comp (ref "U12")
      (value "IC_BITFURY16")
      (footprint "SMD_QFN50P600X600X175-36AN")
      (description "BitFury 2016 16 nm")
      (libsource (lib "BitCoin") (part "IC_BITFURY16"))
    )
  )
  (nets
    (net (code "1") (name "/BF_CLK16") (class "Default")
      (node (ref "U1") (pin "22") (pinfunction "SCK_22") (pintype "passive"))
      (node (ref "U9") (pin "10") (pinfunction "C_0_10") (pintype "passive"))
    )
    (net (code "2") (name "/BF_CLK17") (class "Default")
      (node (ref "U3") (pin "22") (pinfunction "SCK_22") (pintype "passive"))
      (node (ref "U9") (pin "7") (pinfunction "C_1_7") (pintype "passive"))
    )
    (net (code "3") (name "/BF_CLK18") (class "Default")
      (node (ref "U4") (pin "22") (pinfunction "SCK_22") (pintype "passive"))
      (node (ref "U9") (pin "4") (pinfunction "C_2_4") (pintype "passive"))
    )
    (net (code "4") (name "/BF_CLK19") (class "Default")
      (node (ref "U2") (pin "22") (pinfunction "SCK_22") (pintype "passive"))
      (node (ref "U9") (pin "1") (pinfunction "C_3_1") (pintype "passive"))
    )
    (net (code "5") (name "/BF_CLK20") (class "Default")
      (node (ref "U5") (pin "22") (pinfunction "SCK_22") (pintype "passive"))
      (node (ref "U9") (pin "38") (pinfunction "C_4_38") (pintype "passive"))
    )
    (net (code "6") (name "/BF_CLK21") (class "Default")
      (node (ref "U6") (pin "22") (pinfunction "SCK_22") (pintype "passive"))
      (node (ref "U9") (pin "35") (pinfunction "C_5_35") (pintype "passive"))
    )
    (net (code "7") (name "/BF_CLK22") (class "Default")
      (node (ref "U7") (pin "22") (pinfunction "SCK_22") (pintype "passive"))
      (node (ref "U9") (pin "32") (pinfunction "C_6_32") (pintype "passive"))
    )
    (net (code "8") (name "/BF_CLK23") (class "Default")
      (node (ref "U8") (pin "22") (pinfunction "SCK_22") (pintype "passive"))
      (node (ref "U9") (pin "29") (pinfunction "C_7_29") (pintype "passive"))
    )
    (net (code "9") (name "/BF_CLK24") (class "Default")
      (node (ref "U10") (pin "22") (pinfunction "SCK_22") (pintype "passive"))
      (node (ref "U9") (pin "26") (pinfunction "C_8_26") (pintype "passive"))
    )
    (net (code "10") (name "/BF_CLK25") (class "Default")
      (node (ref "U12") (pin "22") (pinfunction "SCK_22") (pintype "passive"))
      (node (ref "U9") (pin "23") (pinfunction "C_9_23") (pintype "passive"))
    )
    (net (code "11") (name "/BF_CLK26") (class "Default")
      (node (ref "U11") (pin "22") (pinfunction "SCK_22") (pintype "passive"))
      (node (ref "U9") (pin "20") (pinfunction "C_10_20") (pintype "passive"))
    )
    (net (code "12") (name "/BF_DAT16") (class "Default")
      (node (ref "U1") (pin "23") (pinfunction "SDATA_23") (pintype "passive"))
      (node (ref "U9") (pin "9") (pinfunction "D_0_9") (pintype "passive"))
    )
    (net (code "13") (name "/BF_DAT17") (class "Default")
      (node (ref "U3") (pin "23") (pinfunction "SDATA_23") (pintype "passive"))
      (node (ref "U9") (pin "6") (pinfunction "D_1_6") (pintype "passive"))
    )
    (net (code "14") (name "/BF_DAT18") (class "Default")
      (node (ref "U4") (pin "23") (pinfunction "SDATA_23") (pintype "passive"))
      (node (ref "U9") (pin "3") (pinfunction "D_2_3") (pintype "passive"))
    )
    (net (code "15") (name "/BF_DAT19") (class "Default")
      (node (ref "U2") (pin "23") (pinfunction "SDATA_23") (pintype "passive"))
      (node (ref "U9") (pin "40") (pinfunction "D_3_40") (pintype "passive"))
    )
    (net (code "16") (name "/BF_DAT20") (class "Default")
      (node (ref "U5") (pin "23") (pinfunction "SDATA_23") (pintype "passive"))
      (node (ref "U9") (pin "37") (pinfunction "D_4_37") (pintype "passive"))
    )
    (net (code "17") (name "/BF_DAT21") (class "Default")
      (node (ref "U6") (pin "23") (pinfunction "SDATA_23") (pintype "passive"))
      (node (ref "U9") (pin "34") (pinfunction "D_5_34") (pintype "passive"))
    )
    (net (code "18") (name "/BF_DAT22") (class "Default")
      (node (ref "U7") (pin "23") (pinfunction "SDATA_23") (pintype "passive"))
      (node (ref "U9") (pin "31") (pinfunction "D_6_31") (pintype "passive"))
    )
    (net (code "19") (name "/BF_DAT23") (class "Default")
      (node (ref "U8") (pin "23") (pinfunction "SDATA_23") (pintype "passive"))
      (node (ref "U9") (pin "28") (pinfunction "D_7_28") (pintype "passive"))
    )
    (net (code "20") (name "/BF_DAT24") (class "Default")
      (node (ref "U10") (pin "23") (pinfunction "SDATA_23") (pintype "passive"))
      (node (ref "U9") (pin "25") (pinfunction "D_8_25") (pintype "passive"))
    )
    (net (code "21") (name "/BF_DAT25") (class "Default")
      (node (ref "U12") (pin "23") (pinfunction "SDATA_23") (pintype "passive"))
      (node (ref "U9") (pin "22") (pinfunction "D_9_22") (pintype "passive"))
    )
    (net (code "22") (name "/BF_DAT26") (class "Default")
      (node (ref "U11") (pin "23") (pinfunction "SDATA_23") (pintype "passive"))
      (node (ref "U9") (pin "19") (pinfunction "D_10_19") (pintype "passive"))
    )
    (net (code "23") (name "/PAR_3") (class "Default")
      (node (ref "U9") (pin "18") (pinfunction "PARITY_18") (pintype "passive"))
    )
    (net (code "24") (name "/PWR16") (class "Default")
      (node (ref "C1") (pin "2") (pinfunction "2_2") (pintype "passive"))
      (node (ref "C13") (pin "2") (pinfunction "2_2") (pintype "passive"))
      (node (ref "C14") (pin "2") (pinfunction "2_2") (pintype "passive"))
      (node (ref "C15") (pin "2") (pinfunction "2_2") (pintype "passive"))
      (node (ref "C2") (pin "2") (pinfunction "2_2") (pintype "passive"))
      (node (ref "C3") (pin "2") (pinfunction "2_2") (pintype "passive"))
      (node (ref "C49") (pin "2") (pinfunction "2_2") (pintype "passive"))
      (node (ref "U1") (pin "36") (pinfunction "EP_36") (pintype "passive"))
      (node (ref "U9") (pin "41") (pinfunction "VSS_41") (pintype "passive"))
    )
    (net (code "25") (name "/PWR17") (class "Default")
      (node (ref "C1") (pin "1") (pinfunction "1_1") (pintype "passive"))
      (node (ref "C13") (pin "1") (pinfunction "1_1") (pintype "passive"))
      (node (ref "C14") (pin "1") (pinfunction "1_1") (pintype "passive"))
      (node (ref "C15") (pin "1") (pinfunction "1_1") (pintype "passive"))
      (node (ref "C16") (pin "2") (pinfunction "2_2") (pintype "passive"))
      (node (ref "C17") (pin "2") (pinfunction "2_2") (pintype "passive"))
      (node (ref "C18") (pin "2") (pinfunction "2_2") (pintype "passive"))
      (node (ref "C2") (pin "1") (pinfunction "1_1") (pintype "passive"))
      (node (ref "C3") (pin "1") (pinfunction "1_1") (pintype "passive"))
      (node (ref "C4") (pin "2") (pinfunction "2_2") (pintype "passive"))
      (node (ref "C5") (pin "2") (pinfunction "2_2") (pintype "passive"))
      (node (ref "C6") (pin "2") (pinfunction "2_2") (pintype "passive"))
      (node (ref "U1") (pin "1") (pinfunction "VDD_1") (pintype "passive"))
      (node (ref "U1") (pin "10") (pinfunction "VDD_10") (pintype "passive"))
      (node (ref "U1") (pin "11") (pinfunction "VDD_11") (pintype "passive"))
      (node (ref "U1") (pin "12") (pinfunction "VDD_12") (pintype "passive"))
      (node (ref "U1") (pin "13") (pinfunction "VDD_13") (pintype "passive"))
      (node (ref "U1") (pin "14") (pinfunction "VDD_14") (pintype "passive"))
      (node (ref "U1") (pin "15") (pinfunction "VDD_15") (pintype "passive"))
      (node (ref "U1") (pin "16") (pinfunction "VDD_16") (pintype "passive"))
      (node (ref "U1") (pin "17") (pinfunction "VDD_17") (pintype "passive"))
      (node (ref "U1") (pin "18") (pinfunction "VDD_18") (pintype "passive"))
      (node (ref "U1") (pin "19") (pinfunction "VDD_19") (pintype "passive"))
      (node (ref "U1") (pin "2") (pinfunction "VDD_2") (pintype "passive"))
      (node (ref "U1") (pin "20") (pinfunction "VDD_20") (pintype "passive"))
      (node (ref "U1") (pin "21") (pinfunction "VDD_21") (pintype "passive"))
      (node (ref "U1") (pin "24") (pinfunction "VDD_24") (pintype "passive"))
      (node (ref "U1") (pin "25") (pinfunction "VDD_25") (pintype "passive"))
      (node (ref "U1") (pin "26") (pinfunction "VDD_26") (pintype "passive"))
      (node (ref "U1") (pin "27") (pinfunction "VDD_27") (pintype "passive"))
      (node (ref "U1") (pin "28") (pinfunction "VDD_28") (pintype "passive"))
      (node (ref "U1") (pin "29") (pinfunction "VDD_29") (pintype "passive"))
      (node (ref "U1") (pin "3") (pinfunction "VDD_3") (pintype "passive"))
      (node (ref "U1") (pin "30") (pinfunction "VDD_30") (pintype "passive"))
      (node (ref "U1") (pin "31") (pinfunction "VDD_31") (pintype "passive"))
      (node (ref "U1") (pin "32") (pinfunction "VDD_32") (pintype "passive"))
      (node (ref "U1") (pin "33") (pinfunction "VDD_33") (pintype "passive"))
      (node (ref "U1") (pin "34") (pinfunction "VDD_34") (pintype "passive"))
      (node (ref "U1") (pin "35") (pinfunction "VDD_35") (pintype "passive"))
      (node (ref "U1") (pin "4") (pinfunction "VDD_4") (pintype "passive"))
      (node (ref "U1") (pin "5") (pinfunction "VDD_5") (pintype "passive"))
      (node (ref "U1") (pin "6") (pinfunction "VDD_6") (pintype "passive"))
      (node (ref "U1") (pin "7") (pinfunction "VDD_7") (pintype "passive"))
      (node (ref "U1") (pin "8") (pinfunction "VDD_8") (pintype "passive"))
      (node (ref "U1") (pin "9") (pinfunction "VDD_9") (pintype "passive"))
      (node (ref "U3") (pin "36") (pinfunction "EP_36") (pintype "passive"))
      (node (ref "U9") (pin "8") (pinfunction "V_0_8") (pintype "passive"))
    )
    (net (code "26") (name "/PWR18") (class "Default")
      (node (ref "C16") (pin "1") (pinfunction "1_1") (pintype "passive"))
      (node (ref "C17") (pin "1") (pinfunction "1_1") (pintype "passive"))
      (node (ref "C18") (pin "1") (pinfunction "1_1") (pintype "passive"))
      (node (ref "C19") (pin "2") (pinfunction "2_2") (pintype "passive"))
      (node (ref "C20") (pin "2") (pinfunction "2_2") (pintype "passive"))
      (node (ref "C21") (pin "2") (pinfunction "2_2") (pintype "passive"))
      (node (ref "C4") (pin "1") (pinfunction "1_1") (pintype "passive"))
      (node (ref "C5") (pin "1") (pinfunction "1_1") (pintype "passive"))
      (node (ref "C6") (pin "1") (pinfunction "1_1") (pintype "passive"))
      (node (ref "C7") (pin "2") (pinfunction "2_2") (pintype "passive"))
      (node (ref "C8") (pin "2") (pinfunction "2_2") (pintype "passive"))
      (node (ref "C9") (pin "2") (pinfunction "2_2") (pintype "passive"))
      (node (ref "U3") (pin "1") (pinfunction "VDD_1") (pintype "passive"))
      (node (ref "U3") (pin "10") (pinfunction "VDD_10") (pintype "passive"))
      (node (ref "U3") (pin "11") (pinfunction "VDD_11") (pintype "passive"))
      (node (ref "U3") (pin "12") (pinfunction "VDD_12") (pintype "passive"))
      (node (ref "U3") (pin "13") (pinfunction "VDD_13") (pintype "passive"))
      (node (ref "U3") (pin "14") (pinfunction "VDD_14") (pintype "passive"))
      (node (ref "U3") (pin "15") (pinfunction "VDD_15") (pintype "passive"))
      (node (ref "U3") (pin "16") (pinfunction "VDD_16") (pintype "passive"))
      (node (ref "U3") (pin "17") (pinfunction "VDD_17") (pintype "passive"))
      (node (ref "U3") (pin "18") (pinfunction "VDD_18") (pintype "passive"))
      (node (ref "U3") (pin "19") (pinfunction "VDD_19") (pintype "passive"))
      (node (ref "U3") (pin "2") (pinfunction "VDD_2") (pintype "passive"))
      (node (ref "U3") (pin "20") (pinfunction "VDD_20") (pintype "passive"))
      (node (ref "U3") (pin "21") (pinfunction "VDD_21") (pintype "passive"))
      (node (ref "U3") (pin "24") (pinfunction "VDD_24") (pintype "passive"))
      (node (ref "U3") (pin "25") (pinfunction "VDD_25") (pintype "passive"))
      (node (ref "U3") (pin "26") (pinfunction "VDD_26") (pintype "passive"))
      (node (ref "U3") (pin "27") (pinfunction "VDD_27") (pintype "passive"))
      (node (ref "U3") (pin "28") (pinfunction "VDD_28") (pintype "passive"))
      (node (ref "U3") (pin "29") (pinfunction "VDD_29") (pintype "passive"))
      (node (ref "U3") (pin "3") (pinfunction "VDD_3") (pintype "passive"))
      (node (ref "U3") (pin "30") (pinfunction "VDD_30") (pintype "passive"))
      (node (ref "U3") (pin "31") (pinfunction "VDD_31") (pintype "passive"))
      (node (ref "U3") (pin "32") (pinfunction "VDD_32") (pintype "passive"))
      (node (ref "U3") (pin "33") (pinfunction "VDD_33") (pintype "passive"))
      (node (ref "U3") (pin "34") (pinfunction "VDD_34") (pintype "passive"))
      (node (ref "U3") (pin "35") (pinfunction "VDD_35") (pintype "passive"))
      (node (ref "U3") (pin "4") (pinfunction "VDD_4") (pintype "passive"))
      (node (ref "U3") (pin "5") (pinfunction "VDD_5") (pintype "passive"))
      (node (ref "U3") (pin "6") (pinfunction "VDD_6") (pintype "passive"))
      (node (ref "U3") (pin "7") (pinfunction "VDD_7") (pintype "passive"))
      (node (ref "U3") (pin "8") (pinfunction "VDD_8") (pintype "passive"))
      (node (ref "U3") (pin "9") (pinfunction "VDD_9") (pintype "passive"))
      (node (ref "U4") (pin "36") (pinfunction "EP_36") (pintype "passive"))
      (node (ref "U9") (pin "5") (pinfunction "V_1_5") (pintype "passive"))
    )
    (net (code "27") (name "/PWR19") (class "Default")
      (node (ref "C10") (pin "2") (pinfunction "2_2") (pintype "passive"))
      (node (ref "C11") (pin "2") (pinfunction "2_2") (pintype "passive"))
      (node (ref "C12") (pin "2") (pinfunction "2_2") (pintype "passive"))
      (node (ref "C19") (pin "1") (pinfunction "1_1") (pintype "passive"))
      (node (ref "C20") (pin "1") (pinfunction "1_1") (pintype "passive"))
      (node (ref "C21") (pin "1") (pinfunction "1_1") (pintype "passive"))
      (node (ref "C22") (pin "2") (pinfunction "2_2") (pintype "passive"))
      (node (ref "C23") (pin "2") (pinfunction "2_2") (pintype "passive"))
      (node (ref "C24") (pin "2") (pinfunction "2_2") (pintype "passive"))
      (node (ref "C7") (pin "1") (pinfunction "1_1") (pintype "passive"))
      (node (ref "C8") (pin "1") (pinfunction "1_1") (pintype "passive"))
      (node (ref "C9") (pin "1") (pinfunction "1_1") (pintype "passive"))
      (node (ref "U2") (pin "36") (pinfunction "EP_36") (pintype "passive"))
      (node (ref "U4") (pin "1") (pinfunction "VDD_1") (pintype "passive"))
      (node (ref "U4") (pin "10") (pinfunction "VDD_10") (pintype "passive"))
      (node (ref "U4") (pin "11") (pinfunction "VDD_11") (pintype "passive"))
      (node (ref "U4") (pin "12") (pinfunction "VDD_12") (pintype "passive"))
      (node (ref "U4") (pin "13") (pinfunction "VDD_13") (pintype "passive"))
      (node (ref "U4") (pin "14") (pinfunction "VDD_14") (pintype "passive"))
      (node (ref "U4") (pin "15") (pinfunction "VDD_15") (pintype "passive"))
      (node (ref "U4") (pin "16") (pinfunction "VDD_16") (pintype "passive"))
      (node (ref "U4") (pin "17") (pinfunction "VDD_17") (pintype "passive"))
      (node (ref "U4") (pin "18") (pinfunction "VDD_18") (pintype "passive"))
      (node (ref "U4") (pin "19") (pinfunction "VDD_19") (pintype "passive"))
      (node (ref "U4") (pin "2") (pinfunction "VDD_2") (pintype "passive"))
      (node (ref "U4") (pin "20") (pinfunction "VDD_20") (pintype "passive"))
      (node (ref "U4") (pin "21") (pinfunction "VDD_21") (pintype "passive"))
      (node (ref "U4") (pin "24") (pinfunction "VDD_24") (pintype "passive"))
      (node (ref "U4") (pin "25") (pinfunction "VDD_25") (pintype "passive"))
      (node (ref "U4") (pin "26") (pinfunction "VDD_26") (pintype "passive"))
      (node (ref "U4") (pin "27") (pinfunction "VDD_27") (pintype "passive"))
      (node (ref "U4") (pin "28") (pinfunction "VDD_28") (pintype "passive"))
      (node (ref "U4") (pin "29") (pinfunction "VDD_29") (pintype "passive"))
      (node (ref "U4") (pin "3") (pinfunction "VDD_3") (pintype "passive"))
      (node (ref "U4") (pin "30") (pinfunction "VDD_30") (pintype "passive"))
      (node (ref "U4") (pin "31") (pinfunction "VDD_31") (pintype "passive"))
      (node (ref "U4") (pin "32") (pinfunction "VDD_32") (pintype "passive"))
      (node (ref "U4") (pin "33") (pinfunction "VDD_33") (pintype "passive"))
      (node (ref "U4") (pin "34") (pinfunction "VDD_34") (pintype "passive"))
      (node (ref "U4") (pin "35") (pinfunction "VDD_35") (pintype "passive"))
      (node (ref "U4") (pin "4") (pinfunction "VDD_4") (pintype "passive"))
      (node (ref "U4") (pin "5") (pinfunction "VDD_5") (pintype "passive"))
      (node (ref "U4") (pin "6") (pinfunction "VDD_6") (pintype "passive"))
      (node (ref "U4") (pin "7") (pinfunction "VDD_7") (pintype "passive"))
      (node (ref "U4") (pin "8") (pinfunction "VDD_8") (pintype "passive"))
      (node (ref "U4") (pin "9") (pinfunction "VDD_9") (pintype "passive"))
      (node (ref "U9") (pin "2") (pinfunction "V_2_2") (pintype "passive"))
    )
    (net (code "28") (name "/PWR20") (class "Default")
      (node (ref "C10") (pin "1") (pinfunction "1_1") (pintype "passive"))
      (node (ref "C11") (pin "1") (pinfunction "1_1") (pintype "passive"))
      (node (ref "C12") (pin "1") (pinfunction "1_1") (pintype "passive"))
      (node (ref "C22") (pin "1") (pinfunction "1_1") (pintype "passive"))
      (node (ref "C23") (pin "1") (pinfunction "1_1") (pintype "passive"))
      (node (ref "C24") (pin "1") (pinfunction "1_1") (pintype "passive"))
      (node (ref "C25") (pin "2") (pinfunction "2_2") (pintype "passive"))
      (node (ref "C26") (pin "2") (pinfunction "2_2") (pintype "passive"))
      (node (ref "C27") (pin "2") (pinfunction "2_2") (pintype "passive"))
      (node (ref "C37") (pin "2") (pinfunction "2_2") (pintype "passive"))
      (node (ref "C38") (pin "2") (pinfunction "2_2") (pintype "passive"))
      (node (ref "C39") (pin "2") (pinfunction "2_2") (pintype "passive"))
      (node (ref "U2") (pin "1") (pinfunction "VDD_1") (pintype "passive"))
      (node (ref "U2") (pin "10") (pinfunction "VDD_10") (pintype "passive"))
      (node (ref "U2") (pin "11") (pinfunction "VDD_11") (pintype "passive"))
      (node (ref "U2") (pin "12") (pinfunction "VDD_12") (pintype "passive"))
      (node (ref "U2") (pin "13") (pinfunction "VDD_13") (pintype "passive"))
      (node (ref "U2") (pin "14") (pinfunction "VDD_14") (pintype "passive"))
      (node (ref "U2") (pin "15") (pinfunction "VDD_15") (pintype "passive"))
      (node (ref "U2") (pin "16") (pinfunction "VDD_16") (pintype "passive"))
      (node (ref "U2") (pin "17") (pinfunction "VDD_17") (pintype "passive"))
      (node (ref "U2") (pin "18") (pinfunction "VDD_18") (pintype "passive"))
      (node (ref "U2") (pin "19") (pinfunction "VDD_19") (pintype "passive"))
      (node (ref "U2") (pin "2") (pinfunction "VDD_2") (pintype "passive"))
      (node (ref "U2") (pin "20") (pinfunction "VDD_20") (pintype "passive"))
      (node (ref "U2") (pin "21") (pinfunction "VDD_21") (pintype "passive"))
      (node (ref "U2") (pin "24") (pinfunction "VDD_24") (pintype "passive"))
      (node (ref "U2") (pin "25") (pinfunction "VDD_25") (pintype "passive"))
      (node (ref "U2") (pin "26") (pinfunction "VDD_26") (pintype "passive"))
      (node (ref "U2") (pin "27") (pinfunction "VDD_27") (pintype "passive"))
      (node (ref "U2") (pin "28") (pinfunction "VDD_28") (pintype "passive"))
      (node (ref "U2") (pin "29") (pinfunction "VDD_29") (pintype "passive"))
      (node (ref "U2") (pin "3") (pinfunction "VDD_3") (pintype "passive"))
      (node (ref "U2") (pin "30") (pinfunction "VDD_30") (pintype "passive"))
      (node (ref "U2") (pin "31") (pinfunction "VDD_31") (pintype "passive"))
      (node (ref "U2") (pin "32") (pinfunction "VDD_32") (pintype "passive"))
      (node (ref "U2") (pin "33") (pinfunction "VDD_33") (pintype "passive"))
      (node (ref "U2") (pin "34") (pinfunction "VDD_34") (pintype "passive"))
      (node (ref "U2") (pin "35") (pinfunction "VDD_35") (pintype "passive"))
      (node (ref "U2") (pin "4") (pinfunction "VDD_4") (pintype "passive"))
      (node (ref "U2") (pin "5") (pinfunction "VDD_5") (pintype "passive"))
      (node (ref "U2") (pin "6") (pinfunction "VDD_6") (pintype "passive"))
      (node (ref "U2") (pin "7") (pinfunction "VDD_7") (pintype "passive"))
      (node (ref "U2") (pin "8") (pinfunction "VDD_8") (pintype "passive"))
      (node (ref "U2") (pin "9") (pinfunction "VDD_9") (pintype "passive"))
      (node (ref "U5") (pin "36") (pinfunction "EP_36") (pintype "passive"))
      (node (ref "U9") (pin "39") (pinfunction "V_3_39") (pintype "passive"))
    )
    (net (code "29") (name "/PWR21") (class "Default")
      (node (ref "C25") (pin "1") (pinfunction "1_1") (pintype "passive"))
      (node (ref "C26") (pin "1") (pinfunction "1_1") (pintype "passive"))
      (node (ref "C27") (pin "1") (pinfunction "1_1") (pintype "passive"))
      (node (ref "C28") (pin "2") (pinfunction "2_2") (pintype "passive"))
      (node (ref "C29") (pin "2") (pinfunction "2_2") (pintype "passive"))
      (node (ref "C30") (pin "2") (pinfunction "2_2") (pintype "passive"))
      (node (ref "C37") (pin "1") (pinfunction "1_1") (pintype "passive"))
      (node (ref "C38") (pin "1") (pinfunction "1_1") (pintype "passive"))
      (node (ref "C39") (pin "1") (pinfunction "1_1") (pintype "passive"))
      (node (ref "C40") (pin "2") (pinfunction "2_2") (pintype "passive"))
      (node (ref "C41") (pin "2") (pinfunction "2_2") (pintype "passive"))
      (node (ref "C42") (pin "2") (pinfunction "2_2") (pintype "passive"))
      (node (ref "U5") (pin "1") (pinfunction "VDD_1") (pintype "passive"))
      (node (ref "U5") (pin "10") (pinfunction "VDD_10") (pintype "passive"))
      (node (ref "U5") (pin "11") (pinfunction "VDD_11") (pintype "passive"))
      (node (ref "U5") (pin "12") (pinfunction "VDD_12") (pintype "passive"))
      (node (ref "U5") (pin "13") (pinfunction "VDD_13") (pintype "passive"))
      (node (ref "U5") (pin "14") (pinfunction "VDD_14") (pintype "passive"))
      (node (ref "U5") (pin "15") (pinfunction "VDD_15") (pintype "passive"))
      (node (ref "U5") (pin "16") (pinfunction "VDD_16") (pintype "passive"))
      (node (ref "U5") (pin "17") (pinfunction "VDD_17") (pintype "passive"))
      (node (ref "U5") (pin "18") (pinfunction "VDD_18") (pintype "passive"))
      (node (ref "U5") (pin "19") (pinfunction "VDD_19") (pintype "passive"))
      (node (ref "U5") (pin "2") (pinfunction "VDD_2") (pintype "passive"))
      (node (ref "U5") (pin "20") (pinfunction "VDD_20") (pintype "passive"))
      (node (ref "U5") (pin "21") (pinfunction "VDD_21") (pintype "passive"))
      (node (ref "U5") (pin "24") (pinfunction "VDD_24") (pintype "passive"))
      (node (ref "U5") (pin "25") (pinfunction "VDD_25") (pintype "passive"))
      (node (ref "U5") (pin "26") (pinfunction "VDD_26") (pintype "passive"))
      (node (ref "U5") (pin "27") (pinfunction "VDD_27") (pintype "passive"))
      (node (ref "U5") (pin "28") (pinfunction "VDD_28") (pintype "passive"))
      (node (ref "U5") (pin "29") (pinfunction "VDD_29") (pintype "passive"))
      (node (ref "U5") (pin "3") (pinfunction "VDD_3") (pintype "passive"))
      (node (ref "U5") (pin "30") (pinfunction "VDD_30") (pintype "passive"))
      (node (ref "U5") (pin "31") (pinfunction "VDD_31") (pintype "passive"))
      (node (ref "U5") (pin "32") (pinfunction "VDD_32") (pintype "passive"))
      (node (ref "U5") (pin "33") (pinfunction "VDD_33") (pintype "passive"))
      (node (ref "U5") (pin "34") (pinfunction "VDD_34") (pintype "passive"))
      (node (ref "U5") (pin "35") (pinfunction "VDD_35") (pintype "passive"))
      (node (ref "U5") (pin "4") (pinfunction "VDD_4") (pintype "passive"))
      (node (ref "U5") (pin "5") (pinfunction "VDD_5") (pintype "passive"))
      (node (ref "U5") (pin "6") (pinfunction "VDD_6") (pintype "passive"))
      (node (ref "U5") (pin "7") (pinfunction "VDD_7") (pintype "passive"))
      (node (ref "U5") (pin "8") (pinfunction "VDD_8") (pintype "passive"))
      (node (ref "U5") (pin "9") (pinfunction "VDD_9") (pintype "passive"))
      (node (ref "U6") (pin "36") (pinfunction "EP_36") (pintype "passive"))
      (node (ref "U9") (pin "36") (pinfunction "V_4_36") (pintype "passive"))
    )
    (net (code "30") (name "/PWR22") (class "Default")
      (node (ref "C28") (pin "1") (pinfunction "1_1") (pintype "passive"))
      (node (ref "C29") (pin "1") (pinfunction "1_1") (pintype "passive"))
      (node (ref "C30") (pin "1") (pinfunction "1_1") (pintype "passive"))
      (node (ref "C31") (pin "2") (pinfunction "2_2") (pintype "passive"))
      (node (ref "C32") (pin "2") (pinfunction "2_2") (pintype "passive"))
      (node (ref "C33") (pin "2") (pinfunction "2_2") (pintype "passive"))
      (node (ref "C40") (pin "1") (pinfunction "1_1") (pintype "passive"))
      (node (ref "C41") (pin "1") (pinfunction "1_1") (pintype "passive"))
      (node (ref "C42") (pin "1") (pinfunction "1_1") (pintype "passive"))
      (node (ref "C43") (pin "2") (pinfunction "2_2") (pintype "passive"))
      (node (ref "C44") (pin "2") (pinfunction "2_2") (pintype "passive"))
      (node (ref "C45") (pin "2") (pinfunction "2_2") (pintype "passive"))
      (node (ref "U6") (pin "1") (pinfunction "VDD_1") (pintype "passive"))
      (node (ref "U6") (pin "10") (pinfunction "VDD_10") (pintype "passive"))
      (node (ref "U6") (pin "11") (pinfunction "VDD_11") (pintype "passive"))
      (node (ref "U6") (pin "12") (pinfunction "VDD_12") (pintype "passive"))
      (node (ref "U6") (pin "13") (pinfunction "VDD_13") (pintype "passive"))
      (node (ref "U6") (pin "14") (pinfunction "VDD_14") (pintype "passive"))
      (node (ref "U6") (pin "15") (pinfunction "VDD_15") (pintype "passive"))
      (node (ref "U6") (pin "16") (pinfunction "VDD_16") (pintype "passive"))
      (node (ref "U6") (pin "17") (pinfunction "VDD_17") (pintype "passive"))
      (node (ref "U6") (pin "18") (pinfunction "VDD_18") (pintype "passive"))
      (node (ref "U6") (pin "19") (pinfunction "VDD_19") (pintype "passive"))
      (node (ref "U6") (pin "2") (pinfunction "VDD_2") (pintype "passive"))
      (node (ref "U6") (pin "20") (pinfunction "VDD_20") (pintype "passive"))
      (node (ref "U6") (pin "21") (pinfunction "VDD_21") (pintype "passive"))
      (node (ref "U6") (pin "24") (pinfunction "VDD_24") (pintype "passive"))
      (node (ref "U6") (pin "25") (pinfunction "VDD_25") (pintype "passive"))
      (node (ref "U6") (pin "26") (pinfunction "VDD_26") (pintype "passive"))
      (node (ref "U6") (pin "27") (pinfunction "VDD_27") (pintype "passive"))
      (node (ref "U6") (pin "28") (pinfunction "VDD_28") (pintype "passive"))
      (node (ref "U6") (pin "29") (pinfunction "VDD_29") (pintype "passive"))
      (node (ref "U6") (pin "3") (pinfunction "VDD_3") (pintype "passive"))
      (node (ref "U6") (pin "30") (pinfunction "VDD_30") (pintype "passive"))
      (node (ref "U6") (pin "31") (pinfunction "VDD_31") (pintype "passive"))
      (node (ref "U6") (pin "32") (pinfunction "VDD_32") (pintype "passive"))
      (node (ref "U6") (pin "33") (pinfunction "VDD_33") (pintype "passive"))
      (node (ref "U6") (pin "34") (pinfunction "VDD_34") (pintype "passive"))
      (node (ref "U6") (pin "35") (pinfunction "VDD_35") (pintype "passive"))
      (node (ref "U6") (pin "4") (pinfunction "VDD_4") (pintype "passive"))
      (node (ref "U6") (pin "5") (pinfunction "VDD_5") (pintype "passive"))
      (node (ref "U6") (pin "6") (pinfunction "VDD_6") (pintype "passive"))
      (node (ref "U6") (pin "7") (pinfunction "VDD_7") (pintype "passive"))
      (node (ref "U6") (pin "8") (pinfunction "VDD_8") (pintype "passive"))
      (node (ref "U6") (pin "9") (pinfunction "VDD_9") (pintype "passive"))
      (node (ref "U7") (pin "36") (pinfunction "EP_36") (pintype "passive"))
      (node (ref "U9") (pin "33") (pinfunction "V_5_33") (pintype "passive"))
    )
    (net (code "31") (name "/PWR23") (class "Default")
      (node (ref "C31") (pin "1") (pinfunction "1_1") (pintype "passive"))
      (node (ref "C32") (pin "1") (pinfunction "1_1") (pintype "passive"))
      (node (ref "C33") (pin "1") (pinfunction "1_1") (pintype "passive"))
      (node (ref "C34") (pin "2") (pinfunction "2_2") (pintype "passive"))
      (node (ref "C35") (pin "2") (pinfunction "2_2") (pintype "passive"))
      (node (ref "C36") (pin "2") (pinfunction "2_2") (pintype "passive"))
      (node (ref "C43") (pin "1") (pinfunction "1_1") (pintype "passive"))
      (node (ref "C44") (pin "1") (pinfunction "1_1") (pintype "passive"))
      (node (ref "C45") (pin "1") (pinfunction "1_1") (pintype "passive"))
      (node (ref "C46") (pin "2") (pinfunction "2_2") (pintype "passive"))
      (node (ref "C47") (pin "2") (pinfunction "2_2") (pintype "passive"))
      (node (ref "C48") (pin "2") (pinfunction "2_2") (pintype "passive"))
      (node (ref "U7") (pin "1") (pinfunction "VDD_1") (pintype "passive"))
      (node (ref "U7") (pin "10") (pinfunction "VDD_10") (pintype "passive"))
      (node (ref "U7") (pin "11") (pinfunction "VDD_11") (pintype "passive"))
      (node (ref "U7") (pin "12") (pinfunction "VDD_12") (pintype "passive"))
      (node (ref "U7") (pin "13") (pinfunction "VDD_13") (pintype "passive"))
      (node (ref "U7") (pin "14") (pinfunction "VDD_14") (pintype "passive"))
      (node (ref "U7") (pin "15") (pinfunction "VDD_15") (pintype "passive"))
      (node (ref "U7") (pin "16") (pinfunction "VDD_16") (pintype "passive"))
      (node (ref "U7") (pin "17") (pinfunction "VDD_17") (pintype "passive"))
      (node (ref "U7") (pin "18") (pinfunction "VDD_18") (pintype "passive"))
      (node (ref "U7") (pin "19") (pinfunction "VDD_19") (pintype "passive"))
      (node (ref "U7") (pin "2") (pinfunction "VDD_2") (pintype "passive"))
      (node (ref "U7") (pin "20") (pinfunction "VDD_20") (pintype "passive"))
      (node (ref "U7") (pin "21") (pinfunction "VDD_21") (pintype "passive"))
      (node (ref "U7") (pin "24") (pinfunction "VDD_24") (pintype "passive"))
      (node (ref "U7") (pin "25") (pinfunction "VDD_25") (pintype "passive"))
      (node (ref "U7") (pin "26") (pinfunction "VDD_26") (pintype "passive"))
      (node (ref "U7") (pin "27") (pinfunction "VDD_27") (pintype "passive"))
      (node (ref "U7") (pin "28") (pinfunction "VDD_28") (pintype "passive"))
      (node (ref "U7") (pin "29") (pinfunction "VDD_29") (pintype "passive"))
      (node (ref "U7") (pin "3") (pinfunction "VDD_3") (pintype "passive"))
      (node (ref "U7") (pin "30") (pinfunction "VDD_30") (pintype "passive"))
      (node (ref "U7") (pin "31") (pinfunction "VDD_31") (pintype "passive"))
      (node (ref "U7") (pin "32") (pinfunction "VDD_32") (pintype "passive"))
      (node (ref "U7") (pin "33") (pinfunction "VDD_33") (pintype "passive"))
      (node (ref "U7") (pin "34") (pinfunction "VDD_34") (pintype "passive"))
      (node (ref "U7") (pin "35") (pinfunction "VDD_35") (pintype "passive"))
      (node (ref "U7") (pin "4") (pinfunction "VDD_4") (pintype "passive"))
      (node (ref "U7") (pin "5") (pinfunction "VDD_5") (pintype "passive"))
      (node (ref "U7") (pin "6") (pinfunction "VDD_6") (pintype "passive"))
      (node (ref "U7") (pin "7") (pinfunction "VDD_7") (pintype "passive"))
      (node (ref "U7") (pin "8") (pinfunction "VDD_8") (pintype "passive"))
      (node (ref "U7") (pin "9") (pinfunction "VDD_9") (pintype "passive"))
      (node (ref "U8") (pin "36") (pinfunction "EP_36") (pintype "passive"))
      (node (ref "U9") (pin "30") (pinfunction "V_6_30") (pintype "passive"))
    )
    (net (code "32") (name "/PWR24") (class "Default")
      (node (ref "C34") (pin "1") (pinfunction "1_1") (pintype "passive"))
      (node (ref "C35") (pin "1") (pinfunction "1_1") (pintype "passive"))
      (node (ref "C36") (pin "1") (pinfunction "1_1") (pintype "passive"))
      (node (ref "C46") (pin "1") (pinfunction "1_1") (pintype "passive"))
      (node (ref "C47") (pin "1") (pinfunction "1_1") (pintype "passive"))
      (node (ref "C48") (pin "1") (pinfunction "1_1") (pintype "passive"))
      (node (ref "C50") (pin "2") (pinfunction "2_2") (pintype "passive"))
      (node (ref "C51") (pin "2") (pinfunction "2_2") (pintype "passive"))
      (node (ref "C52") (pin "2") (pinfunction "2_2") (pintype "passive"))
      (node (ref "C59") (pin "2") (pinfunction "2_2") (pintype "passive"))
      (node (ref "C60") (pin "2") (pinfunction "2_2") (pintype "passive"))
      (node (ref "C61") (pin "2") (pinfunction "2_2") (pintype "passive"))
      (node (ref "U10") (pin "36") (pinfunction "EP_36") (pintype "passive"))
      (node (ref "U8") (pin "1") (pinfunction "VDD_1") (pintype "passive"))
      (node (ref "U8") (pin "10") (pinfunction "VDD_10") (pintype "passive"))
      (node (ref "U8") (pin "11") (pinfunction "VDD_11") (pintype "passive"))
      (node (ref "U8") (pin "12") (pinfunction "VDD_12") (pintype "passive"))
      (node (ref "U8") (pin "13") (pinfunction "VDD_13") (pintype "passive"))
      (node (ref "U8") (pin "14") (pinfunction "VDD_14") (pintype "passive"))
      (node (ref "U8") (pin "15") (pinfunction "VDD_15") (pintype "passive"))
      (node (ref "U8") (pin "16") (pinfunction "VDD_16") (pintype "passive"))
      (node (ref "U8") (pin "17") (pinfunction "VDD_17") (pintype "passive"))
      (node (ref "U8") (pin "18") (pinfunction "VDD_18") (pintype "passive"))
      (node (ref "U8") (pin "19") (pinfunction "VDD_19") (pintype "passive"))
      (node (ref "U8") (pin "2") (pinfunction "VDD_2") (pintype "passive"))
      (node (ref "U8") (pin "20") (pinfunction "VDD_20") (pintype "passive"))
      (node (ref "U8") (pin "21") (pinfunction "VDD_21") (pintype "passive"))
      (node (ref "U8") (pin "24") (pinfunction "VDD_24") (pintype "passive"))
      (node (ref "U8") (pin "25") (pinfunction "VDD_25") (pintype "passive"))
      (node (ref "U8") (pin "26") (pinfunction "VDD_26") (pintype "passive"))
      (node (ref "U8") (pin "27") (pinfunction "VDD_27") (pintype "passive"))
      (node (ref "U8") (pin "28") (pinfunction "VDD_28") (pintype "passive"))
      (node (ref "U8") (pin "29") (pinfunction "VDD_29") (pintype "passive"))
      (node (ref "U8") (pin "3") (pinfunction "VDD_3") (pintype "passive"))
      (node (ref "U8") (pin "30") (pinfunction "VDD_30") (pintype "passive"))
      (node (ref "U8") (pin "31") (pinfunction "VDD_31") (pintype "passive"))
      (node (ref "U8") (pin "32") (pinfunction "VDD_32") (pintype "passive"))
      (node (ref "U8") (pin "33") (pinfunction "VDD_33") (pintype "passive"))
      (node (ref "U8") (pin "34") (pinfunction "VDD_34") (pintype "passive"))
      (node (ref "U8") (pin "35") (pinfunction "VDD_35") (pintype "passive"))
      (node (ref "U8") (pin "4") (pinfunction "VDD_4") (pintype "passive"))
      (node (ref "U8") (pin "5") (pinfunction "VDD_5") (pintype "passive"))
      (node (ref "U8") (pin "6") (pinfunction "VDD_6") (pintype "passive"))
      (node (ref "U8") (pin "7") (pinfunction "VDD_7") (pintype "passive"))
      (node (ref "U8") (pin "8") (pinfunction "VDD_8") (pintype "passive"))
      (node (ref "U8") (pin "9") (pinfunction "VDD_9") (pintype "passive"))
      (node (ref "U9") (pin "27") (pinfunction "V_7_27") (pintype "passive"))
    )
    (net (code "33") (name "/PWR25") (class "Default")
      (node (ref "C50") (pin "1") (pinfunction "1_1") (pintype "passive"))
      (node (ref "C51") (pin "1") (pinfunction "1_1") (pintype "passive"))
      (node (ref "C52") (pin "1") (pinfunction "1_1") (pintype "passive"))
      (node (ref "C53") (pin "2") (pinfunction "2_2") (pintype "passive"))
      (node (ref "C54") (pin "2") (pinfunction "2_2") (pintype "passive"))
      (node (ref "C55") (pin "2") (pinfunction "2_2") (pintype "passive"))
      (node (ref "C59") (pin "1") (pinfunction "1_1") (pintype "passive"))
      (node (ref "C60") (pin "1") (pinfunction "1_1") (pintype "passive"))
      (node (ref "C61") (pin "1") (pinfunction "1_1") (pintype "passive"))
      (node (ref "C62") (pin "2") (pinfunction "2_2") (pintype "passive"))
      (node (ref "C63") (pin "2") (pinfunction "2_2") (pintype "passive"))
      (node (ref "C64") (pin "2") (pinfunction "2_2") (pintype "passive"))
      (node (ref "U10") (pin "1") (pinfunction "VDD_1") (pintype "passive"))
      (node (ref "U10") (pin "10") (pinfunction "VDD_10") (pintype "passive"))
      (node (ref "U10") (pin "11") (pinfunction "VDD_11") (pintype "passive"))
      (node (ref "U10") (pin "12") (pinfunction "VDD_12") (pintype "passive"))
      (node (ref "U10") (pin "13") (pinfunction "VDD_13") (pintype "passive"))
      (node (ref "U10") (pin "14") (pinfunction "VDD_14") (pintype "passive"))
      (node (ref "U10") (pin "15") (pinfunction "VDD_15") (pintype "passive"))
      (node (ref "U10") (pin "16") (pinfunction "VDD_16") (pintype "passive"))
      (node (ref "U10") (pin "17") (pinfunction "VDD_17") (pintype "passive"))
      (node (ref "U10") (pin "18") (pinfunction "VDD_18") (pintype "passive"))
      (node (ref "U10") (pin "19") (pinfunction "VDD_19") (pintype "passive"))
      (node (ref "U10") (pin "2") (pinfunction "VDD_2") (pintype "passive"))
      (node (ref "U10") (pin "20") (pinfunction "VDD_20") (pintype "passive"))
      (node (ref "U10") (pin "21") (pinfunction "VDD_21") (pintype "passive"))
      (node (ref "U10") (pin "24") (pinfunction "VDD_24") (pintype "passive"))
      (node (ref "U10") (pin "25") (pinfunction "VDD_25") (pintype "passive"))
      (node (ref "U10") (pin "26") (pinfunction "VDD_26") (pintype "passive"))
      (node (ref "U10") (pin "27") (pinfunction "VDD_27") (pintype "passive"))
      (node (ref "U10") (pin "28") (pinfunction "VDD_28") (pintype "passive"))
      (node (ref "U10") (pin "29") (pinfunction "VDD_29") (pintype "passive"))
      (node (ref "U10") (pin "3") (pinfunction "VDD_3") (pintype "passive"))
      (node (ref "U10") (pin "30") (pinfunction "VDD_30") (pintype "passive"))
      (node (ref "U10") (pin "31") (pinfunction "VDD_31") (pintype "passive"))
      (node (ref "U10") (pin "32") (pinfunction "VDD_32") (pintype "passive"))
      (node (ref "U10") (pin "33") (pinfunction "VDD_33") (pintype "passive"))
      (node (ref "U10") (pin "34") (pinfunction "VDD_34") (pintype "passive"))
      (node (ref "U10") (pin "35") (pinfunction "VDD_35") (pintype "passive"))
      (node (ref "U10") (pin "4") (pinfunction "VDD_4") (pintype "passive"))
      (node (ref "U10") (pin "5") (pinfunction "VDD_5") (pintype "passive"))
      (node (ref "U10") (pin "6") (pinfunction "VDD_6") (pintype "passive"))
      (node (ref "U10") (pin "7") (pinfunction "VDD_7") (pintype "passive"))
      (node (ref "U10") (pin "8") (pinfunction "VDD_8") (pintype "passive"))
      (node (ref "U10") (pin "9") (pinfunction "VDD_9") (pintype "passive"))
      (node (ref "U12") (pin "36") (pinfunction "EP_36") (pintype "passive"))
      (node (ref "U9") (pin "24") (pinfunction "V_8_24") (pintype "passive"))
    )
    (net (code "34") (name "/PWR26") (class "Default")
      (node (ref "C53") (pin "1") (pinfunction "1_1") (pintype "passive"))
      (node (ref "C54") (pin "1") (pinfunction "1_1") (pintype "passive"))
      (node (ref "C55") (pin "1") (pinfunction "1_1") (pintype "passive"))
      (node (ref "C56") (pin "2") (pinfunction "2_2") (pintype "passive"))
      (node (ref "C57") (pin "2") (pinfunction "2_2") (pintype "passive"))
      (node (ref "C58") (pin "2") (pinfunction "2_2") (pintype "passive"))
      (node (ref "C62") (pin "1") (pinfunction "1_1") (pintype "passive"))
      (node (ref "C63") (pin "1") (pinfunction "1_1") (pintype "passive"))
      (node (ref "C64") (pin "1") (pinfunction "1_1") (pintype "passive"))
      (node (ref "C65") (pin "2") (pinfunction "2_2") (pintype "passive"))
      (node (ref "C66") (pin "2") (pinfunction "2_2") (pintype "passive"))
      (node (ref "C67") (pin "2") (pinfunction "2_2") (pintype "passive"))
      (node (ref "U11") (pin "36") (pinfunction "EP_36") (pintype "passive"))
      (node (ref "U12") (pin "1") (pinfunction "VDD_1") (pintype "passive"))
      (node (ref "U12") (pin "10") (pinfunction "VDD_10") (pintype "passive"))
      (node (ref "U12") (pin "11") (pinfunction "VDD_11") (pintype "passive"))
      (node (ref "U12") (pin "12") (pinfunction "VDD_12") (pintype "passive"))
      (node (ref "U12") (pin "13") (pinfunction "VDD_13") (pintype "passive"))
      (node (ref "U12") (pin "14") (pinfunction "VDD_14") (pintype "passive"))
      (node (ref "U12") (pin "15") (pinfunction "VDD_15") (pintype "passive"))
      (node (ref "U12") (pin "16") (pinfunction "VDD_16") (pintype "passive"))
      (node (ref "U12") (pin "17") (pinfunction "VDD_17") (pintype "passive"))
      (node (ref "U12") (pin "18") (pinfunction "VDD_18") (pintype "passive"))
      (node (ref "U12") (pin "19") (pinfunction "VDD_19") (pintype "passive"))
      (node (ref "U12") (pin "2") (pinfunction "VDD_2") (pintype "passive"))
      (node (ref "U12") (pin "20") (pinfunction "VDD_20") (pintype "passive"))
      (node (ref "U12") (pin "21") (pinfunction "VDD_21") (pintype "passive"))
      (node (ref "U12") (pin "24") (pinfunction "VDD_24") (pintype "passive"))
      (node (ref "U12") (pin "25") (pinfunction "VDD_25") (pintype "passive"))
      (node (ref "U12") (pin "26") (pinfunction "VDD_26") (pintype "passive"))
      (node (ref "U12") (pin "27") (pinfunction "VDD_27") (pintype "passive"))
      (node (ref "U12") (pin "28") (pinfunction "VDD_28") (pintype "passive"))
      (node (ref "U12") (pin "29") (pinfunction "VDD_29") (pintype "passive"))
      (node (ref "U12") (pin "3") (pinfunction "VDD_3") (pintype "passive"))
      (node (ref "U12") (pin "30") (pinfunction "VDD_30") (pintype "passive"))
      (node (ref "U12") (pin "31") (pinfunction "VDD_31") (pintype "passive"))
      (node (ref "U12") (pin "32") (pinfunction "VDD_32") (pintype "passive"))
      (node (ref "U12") (pin "33") (pinfunction "VDD_33") (pintype "passive"))
      (node (ref "U12") (pin "34") (pinfunction "VDD_34") (pintype "passive"))
      (node (ref "U12") (pin "35") (pinfunction "VDD_35") (pintype "passive"))
      (node (ref "U12") (pin "4") (pinfunction "VDD_4") (pintype "passive"))
      (node (ref "U12") (pin "5") (pinfunction "VDD_5") (pintype "passive"))
      (node (ref "U12") (pin "6") (pinfunction "VDD_6") (pintype "passive"))
      (node (ref "U12") (pin "7") (pinfunction "VDD_7") (pintype "passive"))
      (node (ref "U12") (pin "8") (pinfunction "VDD_8") (pintype "passive"))
      (node (ref "U12") (pin "9") (pinfunction "VDD_9") (pintype "passive"))
      (node (ref "U9") (pin "21") (pinfunction "V_9_21") (pintype "passive"))
    )
    (net (code "35") (name "/RX0_3") (class "Default")
      (node (ref "U9") (pin "12") (pinfunction "RX_0_12") (pintype "passive"))
    )
    (net (code "36") (name "/RX1_3") (class "Default")
      (node (ref "U9") (pin "14") (pinfunction "RX_1_14") (pintype "passive"))
    )
    (net (code "37") (name "/RX2_3") (class "Default")
      (node (ref "U9") (pin "16") (pinfunction "RX_2_16") (pintype "passive"))
    )
    (net (code "38") (name "/TX0_3") (class "Default")
      (node (ref "U9") (pin "11") (pinfunction "TX_0_11") (pintype "passive"))
    )
    (net (code "39") (name "/TX1_3") (class "Default")
      (node (ref "U9") (pin "13") (pinfunction "TX_1_13") (pintype "passive"))
    )
    (net (code "40") (name "/TX2_3") (class "Default")
      (node (ref "U9") (pin "15") (pinfunction "TX_2_15") (pintype "passive"))
    )
    (net (code "41") (name "/VCC") (class "Default")
      (node (ref "C49") (pin "1") (pinfunction "1_1") (pintype "passive"))
      (node (ref "C56") (pin "1") (pinfunction "1_1") (pintype "passive"))
      (node (ref "C57") (pin "1") (pinfunction "1_1") (pintype "passive"))
      (node (ref "C58") (pin "1") (pinfunction "1_1") (pintype "passive"))
      (node (ref "C65") (pin "1") (pinfunction "1_1") (pintype "passive"))
      (node (ref "C66") (pin "1") (pinfunction "1_1") (pintype "passive"))
      (node (ref "C67") (pin "1") (pinfunction "1_1") (pintype "passive"))
      (node (ref "U11") (pin "1") (pinfunction "VDD_1") (pintype "passive"))
      (node (ref "U11") (pin "10") (pinfunction "VDD_10") (pintype "passive"))
      (node (ref "U11") (pin "11") (pinfunction "VDD_11") (pintype "passive"))
      (node (ref "U11") (pin "12") (pinfunction "VDD_12") (pintype "passive"))
      (node (ref "U11") (pin "13") (pinfunction "VDD_13") (pintype "passive"))
      (node (ref "U11") (pin "14") (pinfunction "VDD_14") (pintype "passive"))
      (node (ref "U11") (pin "15") (pinfunction "VDD_15") (pintype "passive"))
      (node (ref "U11") (pin "16") (pinfunction "VDD_16") (pintype "passive"))
      (node (ref "U11") (pin "17") (pinfunction "VDD_17") (pintype "passive"))
      (node (ref "U11") (pin "18") (pinfunction "VDD_18") (pintype "passive"))
      (node (ref "U11") (pin "19") (pinfunction "VDD_19") (pintype "passive"))
      (node (ref "U11") (pin "2") (pinfunction "VDD_2") (pintype "passive"))
      (node (ref "U11") (pin "20") (pinfunction "VDD_20") (pintype "passive"))
      (node (ref "U11") (pin "21") (pinfunction "VDD_21") (pintype "passive"))
      (node (ref "U11") (pin "24") (pinfunction "VDD_24") (pintype "passive"))
      (node (ref "U11") (pin "25") (pinfunction "VDD_25") (pintype "passive"))
      (node (ref "U11") (pin "26") (pinfunction "VDD_26") (pintype "passive"))
      (node (ref "U11") (pin "27") (pinfunction "VDD_27") (pintype "passive"))
      (node (ref "U11") (pin "28") (pinfunction "VDD_28") (pintype "passive"))
      (node (ref "U11") (pin "29") (pinfunction "VDD_29") (pintype "passive"))
      (node (ref "U11") (pin "3") (pinfunction "VDD_3") (pintype "passive"))
      (node (ref "U11") (pin "30") (pinfunction "VDD_30") (pintype "passive"))
      (node (ref "U11") (pin "31") (pinfunction "VDD_31") (pintype "passive"))
      (node (ref "U11") (pin "32") (pinfunction "VDD_32") (pintype "passive"))
      (node (ref "U11") (pin "33") (pinfunction "VDD_33") (pintype "passive"))
      (node (ref "U11") (pin "34") (pinfunction "VDD_34") (pintype "passive"))
      (node (ref "U11") (pin "35") (pinfunction "VDD_35") (pintype "passive"))
      (node (ref "U11") (pin "4") (pinfunction "VDD_4") (pintype "passive"))
      (node (ref "U11") (pin "5") (pinfunction "VDD_5") (pintype "passive"))
      (node (ref "U11") (pin "6") (pinfunction "VDD_6") (pintype "passive"))
      (node (ref "U11") (pin "7") (pinfunction "VDD_7") (pintype "passive"))
      (node (ref "U11") (pin "8") (pinfunction "VDD_8") (pintype "passive"))
      (node (ref "U11") (pin "9") (pinfunction "VDD_9") (pintype "passive"))
      (node (ref "U9") (pin "17") (pinfunction "VDD_17") (pintype "passive"))
    )
  )
)
